# Hive_1_6.net
KiCad netlist of a schematic drawn in EAGLE
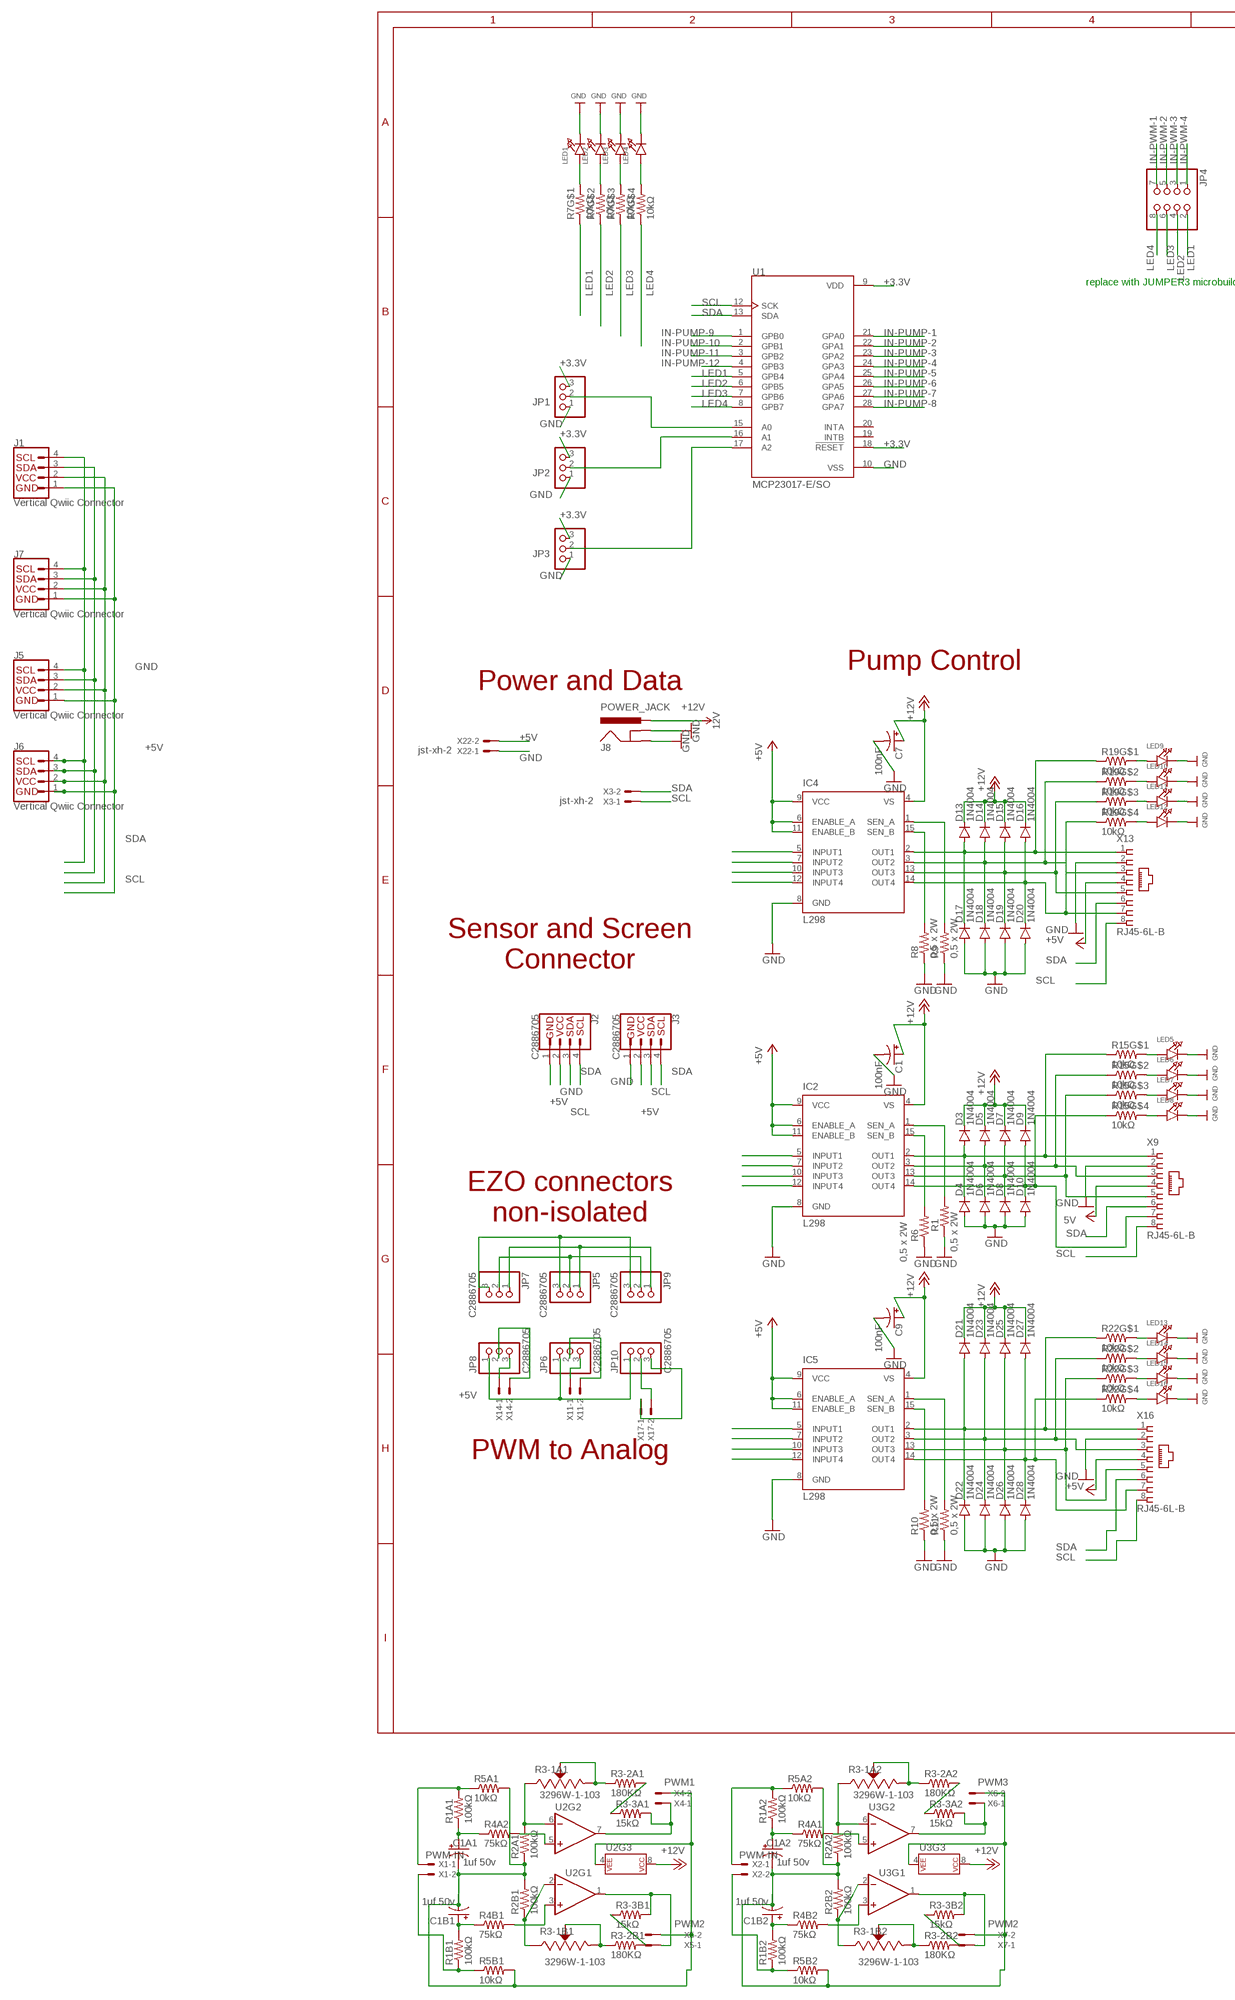
[diagram p0: schematic, sheet 1, part 1 of 2]
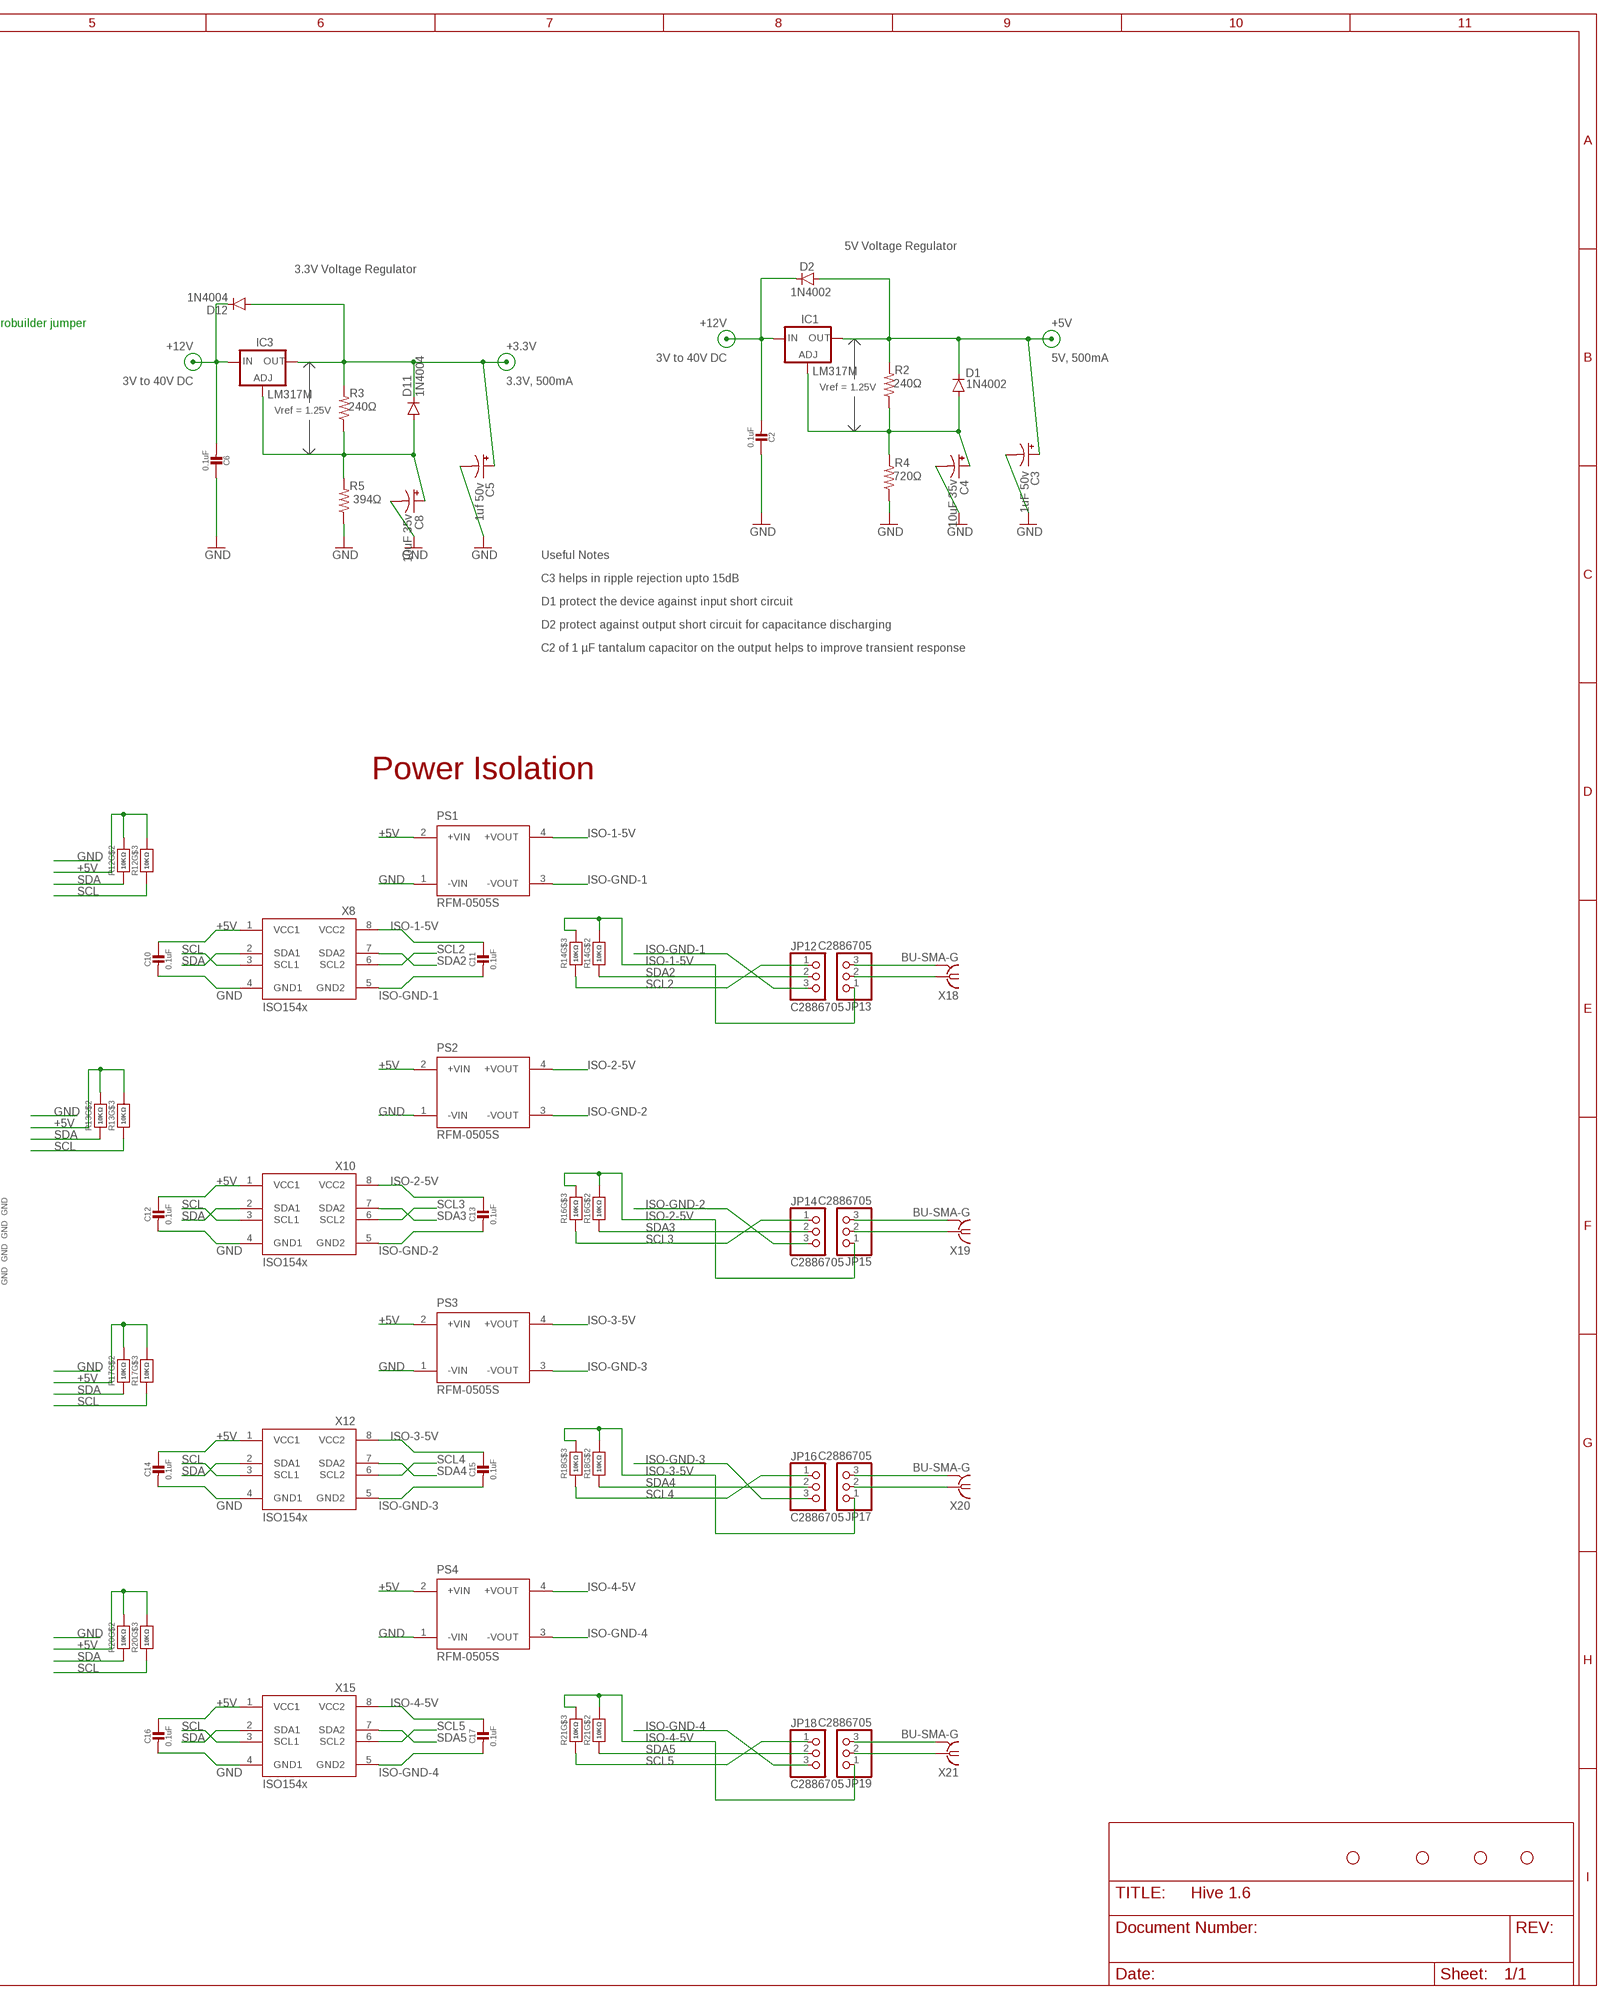
[diagram p1: schematic, sheet 1, part 2 of 2]

(export (version "E")
  (design (tool "Eeschema 10.0.6"))
  (components
    (comp (ref "C1")
      (value "100nF")
      (footprint "eagle-import:UD-4X5,8_NICHICON")
      (libsource (lib "eagle-import") (part "CPOL-USUD-4X5,8"))
    )
    (comp (ref "C1A1")
      (value "1uf 50v")
      (footprint "eagle-import:UD-4X5,8_NICHICON")
      (libsource (lib "eagle-import") (part "CPOL-USUD-4X5,8"))
    )
    (comp (ref "C1A2")
      (value "1uf 50v")
      (footprint "eagle-import:UD-4X5,8_NICHICON")
      (libsource (lib "eagle-import") (part "CPOL-USUD-4X5,8"))
    )
    (comp (ref "C1B1")
      (value "1uf 50v")
      (footprint "eagle-import:UD-4X5,8_NICHICON")
      (libsource (lib "eagle-import") (part "CPOL-USUD-4X5,8"))
    )
    (comp (ref "C1B2")
      (value "1uf 50v")
      (footprint "eagle-import:UD-4X5,8_NICHICON")
      (libsource (lib "eagle-import") (part "CPOL-USUD-4X5,8"))
    )
    (comp (ref "C2")
      (value "0.1uF")
      (footprint "eagle-import:0603-NO")
      (libsource (lib "eagle-import") (part "CAP_CERAMIC0603_NO"))
    )
    (comp (ref "C3")
      (value "1uF 50v")
      (footprint "eagle-import:UD-4X5,8_NICHICON")
      (libsource (lib "eagle-import") (part "CPOL-USUD-4X5,8"))
    )
    (comp (ref "C4")
      (value "10uF 35v")
      (footprint "eagle-import:UD-4X5,8_NICHICON")
      (libsource (lib "eagle-import") (part "CPOL-USUD-4X5,8"))
    )
    (comp (ref "C5")
      (value "1uf 50v")
      (footprint "eagle-import:UD-4X5,8_NICHICON")
      (libsource (lib "eagle-import") (part "CPOL-USUD-4X5,8"))
    )
    (comp (ref "C6")
      (value "0.1uF")
      (footprint "eagle-import:0603-NO")
      (libsource (lib "eagle-import") (part "CAP_CERAMIC0603_NO"))
    )
    (comp (ref "C7")
      (value "100nF")
      (footprint "eagle-import:UD-4X5,8_NICHICON")
      (libsource (lib "eagle-import") (part "CPOL-USUD-4X5,8"))
    )
    (comp (ref "C8")
      (value "10uF 35v")
      (footprint "eagle-import:UD-4X5,8_NICHICON")
      (libsource (lib "eagle-import") (part "CPOL-USUD-4X5,8"))
    )
    (comp (ref "C9")
      (value "100nF")
      (footprint "eagle-import:UD-4X5,8_NICHICON")
      (libsource (lib "eagle-import") (part "CPOL-USUD-4X5,8"))
    )
    (comp (ref "C10")
      (value "0.1uF")
      (footprint "eagle-import:0603-NO")
      (libsource (lib "eagle-import") (part "CAP_CERAMIC0603_NO"))
    )
    (comp (ref "C11")
      (value "0.1uF")
      (footprint "eagle-import:0603-NO")
      (libsource (lib "eagle-import") (part "CAP_CERAMIC0603_NO"))
    )
    (comp (ref "C12")
      (value "0.1uF")
      (footprint "eagle-import:0603-NO")
      (libsource (lib "eagle-import") (part "CAP_CERAMIC0603_NO"))
    )
    (comp (ref "C13")
      (value "0.1uF")
      (footprint "eagle-import:0603-NO")
      (libsource (lib "eagle-import") (part "CAP_CERAMIC0603_NO"))
    )
    (comp (ref "C14")
      (value "0.1uF")
      (footprint "eagle-import:0603-NO")
      (libsource (lib "eagle-import") (part "CAP_CERAMIC0603_NO"))
    )
    (comp (ref "C15")
      (value "0.1uF")
      (footprint "eagle-import:0603-NO")
      (libsource (lib "eagle-import") (part "CAP_CERAMIC0603_NO"))
    )
    (comp (ref "C16")
      (value "0.1uF")
      (footprint "eagle-import:0603-NO")
      (libsource (lib "eagle-import") (part "CAP_CERAMIC0603_NO"))
    )
    (comp (ref "C17")
      (value "0.1uF")
      (footprint "eagle-import:0603-NO")
      (libsource (lib "eagle-import") (part "CAP_CERAMIC0603_NO"))
    )
    (comp (ref "D1")
      (value "1N4002")
      (footprint "eagle-import:DO214BA")
      (libsource (lib "eagle-import") (part "DIODE-DO214BA"))
    )
    (comp (ref "D2")
      (value "1N4002")
      (footprint "eagle-import:DO214BA")
      (libsource (lib "eagle-import") (part "DIODE-DO214BA"))
    )
    (comp (ref "D3")
      (value "1N4004")
      (footprint "eagle-import:DO214BA")
      (libsource (lib "eagle-import") (part "DIODE-DO214BA"))
    )
    (comp (ref "D4")
      (value "1N4004")
      (footprint "eagle-import:DO214BA")
      (libsource (lib "eagle-import") (part "DIODE-DO214BA"))
    )
    (comp (ref "D5")
      (value "1N4004")
      (footprint "eagle-import:DO214BA")
      (libsource (lib "eagle-import") (part "DIODE-DO214BA"))
    )
    (comp (ref "D6")
      (value "1N4004")
      (footprint "eagle-import:DO214BA")
      (libsource (lib "eagle-import") (part "DIODE-DO214BA"))
    )
    (comp (ref "D7")
      (value "1N4004")
      (footprint "eagle-import:DO214BA")
      (libsource (lib "eagle-import") (part "DIODE-DO214BA"))
    )
    (comp (ref "D8")
      (value "1N4004")
      (footprint "eagle-import:DO214BA")
      (libsource (lib "eagle-import") (part "DIODE-DO214BA"))
    )
    (comp (ref "D9")
      (value "1N4004")
      (footprint "eagle-import:DO214BA")
      (libsource (lib "eagle-import") (part "DIODE-DO214BA"))
    )
    (comp (ref "D10")
      (value "1N4004")
      (footprint "eagle-import:DO214BA")
      (libsource (lib "eagle-import") (part "DIODE-DO214BA"))
    )
    (comp (ref "D11")
      (value "1N4004")
      (footprint "eagle-import:DO214BA")
      (libsource (lib "eagle-import") (part "DIODE-DO214BA"))
    )
    (comp (ref "D12")
      (value "1N4004")
      (footprint "eagle-import:DO214BA")
      (libsource (lib "eagle-import") (part "DIODE-DO214BA"))
    )
    (comp (ref "D13")
      (value "1N4004")
      (footprint "eagle-import:DO214BA")
      (libsource (lib "eagle-import") (part "DIODE-DO214BA"))
    )
    (comp (ref "D14")
      (value "1N4004")
      (footprint "eagle-import:DO214BA")
      (libsource (lib "eagle-import") (part "DIODE-DO214BA"))
    )
    (comp (ref "D15")
      (value "1N4004")
      (footprint "eagle-import:DO214BA")
      (libsource (lib "eagle-import") (part "DIODE-DO214BA"))
    )
    (comp (ref "D16")
      (value "1N4004")
      (footprint "eagle-import:DO214BA")
      (libsource (lib "eagle-import") (part "DIODE-DO214BA"))
    )
    (comp (ref "D17")
      (value "1N4004")
      (footprint "eagle-import:DO214BA")
      (libsource (lib "eagle-import") (part "DIODE-DO214BA"))
    )
    (comp (ref "D18")
      (value "1N4004")
      (footprint "eagle-import:DO214BA")
      (libsource (lib "eagle-import") (part "DIODE-DO214BA"))
    )
    (comp (ref "D19")
      (value "1N4004")
      (footprint "eagle-import:DO214BA")
      (libsource (lib "eagle-import") (part "DIODE-DO214BA"))
    )
    (comp (ref "D20")
      (value "1N4004")
      (footprint "eagle-import:DO214BA")
      (libsource (lib "eagle-import") (part "DIODE-DO214BA"))
    )
    (comp (ref "D21")
      (value "1N4004")
      (footprint "eagle-import:DO214BA")
      (libsource (lib "eagle-import") (part "DIODE-DO214BA"))
    )
    (comp (ref "D22")
      (value "1N4004")
      (footprint "eagle-import:DO214BA")
      (libsource (lib "eagle-import") (part "DIODE-DO214BA"))
    )
    (comp (ref "D23")
      (value "1N4004")
      (footprint "eagle-import:DO214BA")
      (libsource (lib "eagle-import") (part "DIODE-DO214BA"))
    )
    (comp (ref "D24")
      (value "1N4004")
      (footprint "eagle-import:DO214BA")
      (libsource (lib "eagle-import") (part "DIODE-DO214BA"))
    )
    (comp (ref "D25")
      (value "1N4004")
      (footprint "eagle-import:DO214BA")
      (libsource (lib "eagle-import") (part "DIODE-DO214BA"))
    )
    (comp (ref "D26")
      (value "1N4004")
      (footprint "eagle-import:DO214BA")
      (libsource (lib "eagle-import") (part "DIODE-DO214BA"))
    )
    (comp (ref "D27")
      (value "1N4004")
      (footprint "eagle-import:DO214BA")
      (libsource (lib "eagle-import") (part "DIODE-DO214BA"))
    )
    (comp (ref "D28")
      (value "1N4004")
      (footprint "eagle-import:DO214BA")
      (libsource (lib "eagle-import") (part "DIODE-DO214BA"))
    )
    (comp (ref "H1")
      (value "STAND-OFF")
      (footprint "eagle-import:STAND-OFF")
      (libsource (lib "eagle-import") (part "STAND-OFF"))
    )
    (comp (ref "H2")
      (value "STAND-OFF")
      (footprint "eagle-import:STAND-OFF")
      (libsource (lib "eagle-import") (part "STAND-OFF"))
    )
    (comp (ref "H3")
      (value "STAND-OFF")
      (footprint "eagle-import:STAND-OFF")
      (libsource (lib "eagle-import") (part "STAND-OFF"))
    )
    (comp (ref "H4")
      (value "STAND-OFF")
      (footprint "eagle-import:STAND-OFF")
      (libsource (lib "eagle-import") (part "STAND-OFF"))
    )
    (comp (ref "IC1")
      (value "LM317MBSTT3")
      (footprint "eagle-import:SOT223")
      (fields (field (name "PARTNUMBER") "LM317M"))
      (libsource (lib "eagle-import") (part "LM317?MBSTT3"))
    )
    (comp (ref "IC2")
      (value "L298")
      (footprint "eagle-import:MULTIWATT-15")
      (fields (field (name "MPN") "L298N"))
      (libsource (lib "eagle-import") (part "L298"))
    )
    (comp (ref "IC3")
      (value "LM317MBSTT3")
      (footprint "eagle-import:SOT223")
      (fields (field (name "PARTNUMBER") "LM317M"))
      (libsource (lib "eagle-import") (part "LM317?MBSTT3"))
    )
    (comp (ref "IC4")
      (value "L298")
      (footprint "eagle-import:MULTIWATT-15")
      (fields (field (name "MPN") "L298N"))
      (libsource (lib "eagle-import") (part "L298"))
    )
    (comp (ref "IC5")
      (value "L298")
      (footprint "eagle-import:MULTIWATT-15")
      (fields (field (name "MPN") "L298N"))
      (libsource (lib "eagle-import") (part "L298"))
    )
    (comp (ref "J1")
      (value "Vertical Qwiic Connector")
      (footprint "eagle-import:JST04_1MM_VERT")
      (libsource (lib "eagle-import") (part "QWIIC_CONNECTOR"))
    )
    (comp (ref "J2")
      (value "C2886705")
      (footprint "eagle-import:1X04")
      (libsource (lib "eagle-import") (part "I2C_STANDARD"))
    )
    (comp (ref "J3")
      (value "C2886705")
      (footprint "eagle-import:1X04")
      (libsource (lib "eagle-import") (part "I2C_STANDARD"))
    )
    (comp (ref "J5")
      (value "Vertical Qwiic Connector")
      (footprint "eagle-import:JST04_1MM_VERT")
      (libsource (lib "eagle-import") (part "QWIIC_CONNECTOR"))
    )
    (comp (ref "J6")
      (value "Vertical Qwiic Connector")
      (footprint "eagle-import:JST04_1MM_VERT")
      (libsource (lib "eagle-import") (part "QWIIC_CONNECTOR"))
    )
    (comp (ref "J7")
      (value "Vertical Qwiic Connector")
      (footprint "eagle-import:JST04_1MM_VERT")
      (libsource (lib "eagle-import") (part "QWIIC_CONNECTOR"))
    )
    (comp (ref "J8")
      (value "POWER_JACK")
      (footprint "eagle-import:POWER_JACK_PTH")
      (libsource (lib "eagle-import") (part "POWER_JACK"))
    )
    (comp (ref "JP1")
      (value "HEADER-1X3ROUND")
      (footprint "eagle-import:1X03_ROUND")
      (libsource (lib "eagle-import") (part "HEADER-1X3ROUND"))
    )
    (comp (ref "JP2")
      (value "HEADER-1X3ROUND")
      (footprint "eagle-import:1X03_ROUND")
      (libsource (lib "eagle-import") (part "HEADER-1X3ROUND"))
    )
    (comp (ref "JP3")
      (value "HEADER-1X3ROUND")
      (footprint "eagle-import:1X03_ROUND")
      (libsource (lib "eagle-import") (part "HEADER-1X3ROUND"))
    )
    (comp (ref "JP4")
      (value "PINHD-2X4")
      (footprint "eagle-import:2X04")
      (libsource (lib "eagle-import") (part "PINHD-2X4"))
    )
    (comp (ref "JP5")
      (value "C2886705")
      (footprint "eagle-import:1X03-CLEANBIG")
      (libsource (lib "eagle-import") (part "PINHD-1X3CB"))
    )
    (comp (ref "JP6")
      (value "C2886705")
      (footprint "eagle-import:1X03-CLEANBIG")
      (libsource (lib "eagle-import") (part "PINHD-1X3CB"))
    )
    (comp (ref "JP7")
      (value "C2886705")
      (footprint "eagle-import:1X03-CLEANBIG")
      (libsource (lib "eagle-import") (part "PINHD-1X3CB"))
    )
    (comp (ref "JP8")
      (value "C2886705")
      (footprint "eagle-import:1X03-CLEANBIG")
      (libsource (lib "eagle-import") (part "PINHD-1X3CB"))
    )
    (comp (ref "JP9")
      (value "C2886705")
      (footprint "eagle-import:1X03-CLEANBIG")
      (libsource (lib "eagle-import") (part "PINHD-1X3CB"))
    )
    (comp (ref "JP10")
      (value "C2886705")
      (footprint "eagle-import:1X03-CLEANBIG")
      (libsource (lib "eagle-import") (part "PINHD-1X3CB"))
    )
    (comp (ref "JP12")
      (value "C2886705")
      (footprint "eagle-import:1X03-CLEANBIG")
      (libsource (lib "eagle-import") (part "PINHD-1X3CB"))
    )
    (comp (ref "JP13")
      (value "C2886705")
      (footprint "eagle-import:1X03-CLEANBIG")
      (libsource (lib "eagle-import") (part "PINHD-1X3CB"))
    )
    (comp (ref "JP14")
      (value "C2886705")
      (footprint "eagle-import:1X03-CLEANBIG")
      (libsource (lib "eagle-import") (part "PINHD-1X3CB"))
    )
    (comp (ref "JP15")
      (value "C2886705")
      (footprint "eagle-import:1X03-CLEANBIG")
      (libsource (lib "eagle-import") (part "PINHD-1X3CB"))
    )
    (comp (ref "JP16")
      (value "C2886705")
      (footprint "eagle-import:1X03-CLEANBIG")
      (libsource (lib "eagle-import") (part "PINHD-1X3CB"))
    )
    (comp (ref "JP17")
      (value "C2886705")
      (footprint "eagle-import:1X03-CLEANBIG")
      (libsource (lib "eagle-import") (part "PINHD-1X3CB"))
    )
    (comp (ref "JP18")
      (value "C2886705")
      (footprint "eagle-import:1X03-CLEANBIG")
      (libsource (lib "eagle-import") (part "PINHD-1X3CB"))
    )
    (comp (ref "JP19")
      (value "C2886705")
      (footprint "eagle-import:1X03-CLEANBIG")
      (libsource (lib "eagle-import") (part "PINHD-1X3CB"))
    )
    (comp (ref "LED1")
      (value "LED0603")
      (footprint "eagle-import:CHIPLED_0603")
      (libsource (lib "eagle-import") (part "LED0603"))
    )
    (comp (ref "LED2")
      (value "LED0603")
      (footprint "eagle-import:CHIPLED_0603")
      (libsource (lib "eagle-import") (part "LED0603"))
    )
    (comp (ref "LED3")
      (value "LED0603")
      (footprint "eagle-import:CHIPLED_0603")
      (libsource (lib "eagle-import") (part "LED0603"))
    )
    (comp (ref "LED4")
      (value "LED0603")
      (footprint "eagle-import:CHIPLED_0603")
      (libsource (lib "eagle-import") (part "LED0603"))
    )
    (comp (ref "LED5")
      (value "LED0603")
      (footprint "eagle-import:CHIPLED_0603")
      (libsource (lib "eagle-import") (part "LED0603"))
    )
    (comp (ref "LED6")
      (value "LED0603")
      (footprint "eagle-import:CHIPLED_0603")
      (libsource (lib "eagle-import") (part "LED0603"))
    )
    (comp (ref "LED7")
      (value "LED0603")
      (footprint "eagle-import:CHIPLED_0603")
      (libsource (lib "eagle-import") (part "LED0603"))
    )
    (comp (ref "LED8")
      (value "LED0603")
      (footprint "eagle-import:CHIPLED_0603")
      (libsource (lib "eagle-import") (part "LED0603"))
    )
    (comp (ref "LED9")
      (value "LED0603")
      (footprint "eagle-import:CHIPLED_0603")
      (libsource (lib "eagle-import") (part "LED0603"))
    )
    (comp (ref "LED10")
      (value "LED0603")
      (footprint "eagle-import:CHIPLED_0603")
      (libsource (lib "eagle-import") (part "LED0603"))
    )
    (comp (ref "LED11")
      (value "LED0603")
      (footprint "eagle-import:CHIPLED_0603")
      (libsource (lib "eagle-import") (part "LED0603"))
    )
    (comp (ref "LED12")
      (value "LED0603")
      (footprint "eagle-import:CHIPLED_0603")
      (libsource (lib "eagle-import") (part "LED0603"))
    )
    (comp (ref "LED13")
      (value "LED0603")
      (footprint "eagle-import:CHIPLED_0603")
      (libsource (lib "eagle-import") (part "LED0603"))
    )
    (comp (ref "LED14")
      (value "LED0603")
      (footprint "eagle-import:CHIPLED_0603")
      (libsource (lib "eagle-import") (part "LED0603"))
    )
    (comp (ref "LED15")
      (value "LED0603")
      (footprint "eagle-import:CHIPLED_0603")
      (libsource (lib "eagle-import") (part "LED0603"))
    )
    (comp (ref "LED16")
      (value "LED0603")
      (footprint "eagle-import:CHIPLED_0603")
      (libsource (lib "eagle-import") (part "LED0603"))
    )
    (comp (ref "PS1")
      (value "RFM-0505S")
      (footprint "eagle-import:CONV_RFM-0505S")
      (fields (field (name "MF") "Recom Power"))
      (libsource (lib "eagle-import") (part "RFM-0505S"))
    )
    (comp (ref "PS2")
      (value "RFM-0505S")
      (footprint "eagle-import:CONV_RFM-0505S")
      (fields (field (name "MF") "Recom Power"))
      (libsource (lib "eagle-import") (part "RFM-0505S"))
    )
    (comp (ref "PS3")
      (value "RFM-0505S")
      (footprint "eagle-import:CONV_RFM-0505S")
      (fields (field (name "MF") "Recom Power"))
      (libsource (lib "eagle-import") (part "RFM-0505S"))
    )
    (comp (ref "PS4")
      (value "RFM-0505S")
      (footprint "eagle-import:CONV_RFM-0505S")
      (fields (field (name "MF") "Recom Power"))
      (libsource (lib "eagle-import") (part "RFM-0505S"))
    )
    (comp (ref "R1")
      (value "0,5 x 2W")
      (footprint "eagle-import:R2512")
      (libsource (lib "eagle-import") (part "R-US_R2512"))
    )
    (comp (ref "R1A1")
      (value "100kΩ")
      (footprint "eagle-import:M1206")
      (libsource (lib "eagle-import") (part "adafruit_420_R-US_M1206"))
    )
    (comp (ref "R1A2")
      (value "100kΩ")
      (footprint "eagle-import:M1206")
      (libsource (lib "eagle-import") (part "adafruit_420_R-US_M1206"))
    )
    (comp (ref "R1B1")
      (value "100kΩ")
      (footprint "eagle-import:M1206")
      (libsource (lib "eagle-import") (part "adafruit_420_R-US_M1206"))
    )
    (comp (ref "R1B2")
      (value "100kΩ")
      (footprint "eagle-import:M1206")
      (libsource (lib "eagle-import") (part "adafruit_420_R-US_M1206"))
    )
    (comp (ref "R2")
      (value "240Ω")
      (footprint "eagle-import:M0805")
      (libsource (lib "eagle-import") (part "resistor_R-US_M0805"))
    )
    (comp (ref "R2A1")
      (value "100kΩ")
      (footprint "eagle-import:M1206")
      (libsource (lib "eagle-import") (part "adafruit_420_R-US_M1206"))
    )
    (comp (ref "R2A2")
      (value "100kΩ")
      (footprint "eagle-import:M1206")
      (libsource (lib "eagle-import") (part "adafruit_420_R-US_M1206"))
    )
    (comp (ref "R2B1")
      (value "100kΩ")
      (footprint "eagle-import:M1206")
      (libsource (lib "eagle-import") (part "adafruit_420_R-US_M1206"))
    )
    (comp (ref "R2B2")
      (value "100kΩ")
      (footprint "eagle-import:M1206")
      (libsource (lib "eagle-import") (part "adafruit_420_R-US_M1206"))
    )
    (comp (ref "R3")
      (value "240Ω")
      (footprint "eagle-import:M0805")
      (libsource (lib "eagle-import") (part "resistor_R-US_M0805"))
    )
    (comp (ref "R3-1A1")
      (value "3296W-1-103")
      (footprint "eagle-import:TRIM_3296W-1-103")
      (fields (field (name "MF") "Bourns"))
      (libsource (lib "eagle-import") (part "3296W-1-103"))
    )
    (comp (ref "R3-1A2")
      (value "3296W-1-103")
      (footprint "eagle-import:TRIM_3296W-1-103")
      (fields (field (name "MF") "Bourns"))
      (libsource (lib "eagle-import") (part "3296W-1-103"))
    )
    (comp (ref "R3-1B1")
      (value "3296W-1-103")
      (footprint "eagle-import:TRIM_3296W-1-103")
      (fields (field (name "MF") "Bourns"))
      (libsource (lib "eagle-import") (part "3296W-1-103"))
    )
    (comp (ref "R3-1B2")
      (value "3296W-1-103")
      (footprint "eagle-import:TRIM_3296W-1-103")
      (fields (field (name "MF") "Bourns"))
      (libsource (lib "eagle-import") (part "3296W-1-103"))
    )
    (comp (ref "R3-2A1")
      (value "180KΩ")
      (footprint "eagle-import:M1206")
      (libsource (lib "eagle-import") (part "adafruit_420_R-US_M1206"))
    )
    (comp (ref "R3-2A2")
      (value "180KΩ")
      (footprint "eagle-import:M1206")
      (libsource (lib "eagle-import") (part "adafruit_420_R-US_M1206"))
    )
    (comp (ref "R3-2B1")
      (value "180KΩ")
      (footprint "eagle-import:M1206")
      (libsource (lib "eagle-import") (part "adafruit_420_R-US_M1206"))
    )
    (comp (ref "R3-2B2")
      (value "180KΩ")
      (footprint "eagle-import:M1206")
      (libsource (lib "eagle-import") (part "adafruit_420_R-US_M1206"))
    )
    (comp (ref "R3-3A1")
      (value "15kΩ")
      (footprint "eagle-import:M1206")
      (libsource (lib "eagle-import") (part "adafruit_420_R-US_M1206"))
    )
    (comp (ref "R3-3A2")
      (value "15kΩ")
      (footprint "eagle-import:M1206")
      (libsource (lib "eagle-import") (part "adafruit_420_R-US_M1206"))
    )
    (comp (ref "R3-3B1")
      (value "15kΩ")
      (footprint "eagle-import:M1206")
      (libsource (lib "eagle-import") (part "adafruit_420_R-US_M1206"))
    )
    (comp (ref "R3-3B2")
      (value "15kΩ")
      (footprint "eagle-import:M1206")
      (libsource (lib "eagle-import") (part "adafruit_420_R-US_M1206"))
    )
    (comp (ref "R4")
      (value "720Ω")
      (footprint "eagle-import:M0805")
      (libsource (lib "eagle-import") (part "resistor_R-US_M0805"))
    )
    (comp (ref "R4A1")
      (value "75kΩ")
      (footprint "eagle-import:M1206")
      (libsource (lib "eagle-import") (part "adafruit_420_R-US_M1206"))
    )
    (comp (ref "R4A2")
      (value "75kΩ")
      (footprint "eagle-import:M1206")
      (libsource (lib "eagle-import") (part "adafruit_420_R-US_M1206"))
    )
    (comp (ref "R4B1")
      (value "75kΩ")
      (footprint "eagle-import:M1206")
      (libsource (lib "eagle-import") (part "adafruit_420_R-US_M1206"))
    )
    (comp (ref "R4B2")
      (value "75kΩ")
      (footprint "eagle-import:M1206")
      (libsource (lib "eagle-import") (part "adafruit_420_R-US_M1206"))
    )
    (comp (ref "R5")
      (value "394Ω")
      (footprint "eagle-import:M0805")
      (libsource (lib "eagle-import") (part "resistor_R-US_M0805"))
    )
    (comp (ref "R5A1")
      (value "10kΩ")
      (footprint "eagle-import:M1206")
      (libsource (lib "eagle-import") (part "adafruit_420_R-US_M1206"))
    )
    (comp (ref "R5A2")
      (value "10kΩ")
      (footprint "eagle-import:M1206")
      (libsource (lib "eagle-import") (part "adafruit_420_R-US_M1206"))
    )
    (comp (ref "R5B1")
      (value "10kΩ")
      (footprint "eagle-import:M1206")
      (libsource (lib "eagle-import") (part "adafruit_420_R-US_M1206"))
    )
    (comp (ref "R5B2")
      (value "10kΩ")
      (footprint "eagle-import:M1206")
      (libsource (lib "eagle-import") (part "adafruit_420_R-US_M1206"))
    )
    (comp (ref "R6")
      (value "0,5 x 2W")
      (footprint "eagle-import:R2512")
      (libsource (lib "eagle-import") (part "R-US_R2512"))
    )
    (comp (ref "R7")
      (value "10kΩ")
      (footprint "eagle-import:RESPACK_4X0603")
      (libsource (lib "eagle-import") (part "RESISTOR_4PACK_US"))
    )
    (comp (ref "R8")
      (value "0,5 x 2W")
      (footprint "eagle-import:R2512")
      (libsource (lib "eagle-import") (part "R-US_R2512"))
    )
    (comp (ref "R9")
      (value "0,5 x 2W")
      (footprint "eagle-import:R2512")
      (libsource (lib "eagle-import") (part "R-US_R2512"))
    )
    (comp (ref "R10")
      (value "0,5 x 2W")
      (footprint "eagle-import:R2512")
      (libsource (lib "eagle-import") (part "R-US_R2512"))
    )
    (comp (ref "R11")
      (value "0,5 x 2W")
      (footprint "eagle-import:R2512")
      (libsource (lib "eagle-import") (part "R-US_R2512"))
    )
    (comp (ref "R12")
      (value "10KΩ")
      (footprint "eagle-import:RESPACK_4X0603")
      (libsource (lib "eagle-import") (part "RESISTOR_4PACK"))
    )
    (comp (ref "R13")
      (value "10KΩ")
      (footprint "eagle-import:RESPACK_4X0603")
      (libsource (lib "eagle-import") (part "RESISTOR_4PACK"))
    )
    (comp (ref "R14")
      (value "10KΩ")
      (footprint "eagle-import:RESPACK_4X0603")
      (libsource (lib "eagle-import") (part "RESISTOR_4PACK"))
    )
    (comp (ref "R15")
      (value "10kΩ")
      (footprint "eagle-import:RESPACK_4X0603")
      (libsource (lib "eagle-import") (part "RESISTOR_4PACK_US"))
    )
    (comp (ref "R16")
      (value "10KΩ")
      (footprint "eagle-import:RESPACK_4X0603")
      (libsource (lib "eagle-import") (part "RESISTOR_4PACK"))
    )
    (comp (ref "R17")
      (value "10KΩ")
      (footprint "eagle-import:RESPACK_4X0603")
      (libsource (lib "eagle-import") (part "RESISTOR_4PACK"))
    )
    (comp (ref "R18")
      (value "10KΩ")
      (footprint "eagle-import:RESPACK_4X0603")
      (libsource (lib "eagle-import") (part "RESISTOR_4PACK"))
    )
    (comp (ref "R19")
      (value "10kΩ")
      (footprint "eagle-import:RESPACK_4X0603")
      (libsource (lib "eagle-import") (part "RESISTOR_4PACK_US"))
    )
    (comp (ref "R20")
      (value "10KΩ")
      (footprint "eagle-import:RESPACK_4X0603")
      (libsource (lib "eagle-import") (part "RESISTOR_4PACK"))
    )
    (comp (ref "R21")
      (value "10KΩ")
      (footprint "eagle-import:RESPACK_4X0603")
      (libsource (lib "eagle-import") (part "RESISTOR_4PACK"))
    )
    (comp (ref "R22")
      (value "10kΩ")
      (footprint "eagle-import:RESPACK_4X0603")
      (libsource (lib "eagle-import") (part "RESISTOR_4PACK_US"))
    )
    (comp (ref "U1")
      (value "MCP23017-E/SO")
      (footprint "eagle-import:SOIC127P1030X265-28N")
      (fields (field (name "MF") "Microchip"))
      (libsource (lib "eagle-import") (part "MCP23017-E/SO"))
    )
    (comp (ref "U2")
      (value "LM358")
      (footprint "eagle-import:SO08")
      (libsource (lib "eagle-import") (part "LM358SO08"))
    )
    (comp (ref "U3")
      (value "LM358")
      (footprint "eagle-import:SO08")
      (libsource (lib "eagle-import") (part "LM358SO08"))
    )
    (comp (ref "X1")
      (value "PWM-IN")
      (footprint "eagle-import:JST-XH-02-PACKAGE-LONG-PAD")
      (libsource (lib "eagle-import") (part "JST-XH-02-PIN-LONG-PAD"))
    )
    (comp (ref "X2")
      (value "PWM-IN")
      (footprint "eagle-import:JST-XH-02-PACKAGE-LONG-PAD")
      (libsource (lib "eagle-import") (part "JST-XH-02-PIN-LONG-PAD"))
    )
    (comp (ref "X3")
      (value "jst-xh-2")
      (footprint "eagle-import:JST-XH-02-PACKAGE-LONG-PAD")
      (libsource (lib "eagle-import") (part "JST-XH-02-PIN-LONG-PAD"))
    )
    (comp (ref "X4")
      (value "PWM1")
      (footprint "eagle-import:JST-XH-02-PACKAGE-LONG-PAD")
      (libsource (lib "eagle-import") (part "JST-XH-02-PIN-LONG-PAD"))
    )
    (comp (ref "X5")
      (value "PWM2")
      (footprint "eagle-import:JST-XH-02-PACKAGE-LONG-PAD")
      (libsource (lib "eagle-import") (part "JST-XH-02-PIN-LONG-PAD"))
    )
    (comp (ref "X6")
      (value "PWM3")
      (footprint "eagle-import:JST-XH-02-PACKAGE-LONG-PAD")
      (libsource (lib "eagle-import") (part "JST-XH-02-PIN-LONG-PAD"))
    )
    (comp (ref "X7")
      (value "PWM2")
      (footprint "eagle-import:JST-XH-02-PACKAGE-LONG-PAD")
      (libsource (lib "eagle-import") (part "JST-XH-02-PIN-LONG-PAD"))
    )
    (comp (ref "X8")
      (value "ISO154X")
      (footprint "eagle-import:SOIC8_150MIL")
      (libsource (lib "eagle-import") (part "ISO154X"))
    )
    (comp (ref "X9")
      (value "RJ45-6L-B")
      (footprint "eagle-import:RJ45-NO-SHIELD")
      (libsource (lib "eagle-import") (part "RJ45-6L-B"))
    )
    (comp (ref "X10")
      (value "ISO154X")
      (footprint "eagle-import:SOIC8_150MIL")
      (libsource (lib "eagle-import") (part "ISO154X"))
    )
    (comp (ref "X11")
      (value "jst-xh-2")
      (footprint "eagle-import:JST-XH-02-PACKAGE-LONG-PAD")
      (libsource (lib "eagle-import") (part "JST-XH-02-PIN-LONG-PAD"))
    )
    (comp (ref "X12")
      (value "ISO154X")
      (footprint "eagle-import:SOIC8_150MIL")
      (libsource (lib "eagle-import") (part "ISO154X"))
    )
    (comp (ref "X13")
      (value "RJ45-6L-B")
      (footprint "eagle-import:RJ45-NO-SHIELD")
      (libsource (lib "eagle-import") (part "RJ45-6L-B"))
    )
    (comp (ref "X14")
      (value "jst-xh-2")
      (footprint "eagle-import:JST-XH-02-PACKAGE-LONG-PAD")
      (libsource (lib "eagle-import") (part "JST-XH-02-PIN-LONG-PAD"))
    )
    (comp (ref "X15")
      (value "ISO154X")
      (footprint "eagle-import:SOIC8_150MIL")
      (libsource (lib "eagle-import") (part "ISO154X"))
    )
    (comp (ref "X16")
      (value "RJ45-6L-B")
      (footprint "eagle-import:RJ45-NO-SHIELD")
      (libsource (lib "eagle-import") (part "RJ45-6L-B"))
    )
    (comp (ref "X17")
      (value "jst-xh-2")
      (footprint "eagle-import:JST-XH-02-PACKAGE-LONG-PAD")
      (libsource (lib "eagle-import") (part "JST-XH-02-PIN-LONG-PAD"))
    )
    (comp (ref "X18")
      (value "BU-SMA-G")
      (footprint "eagle-import:BU-SMA-G")
      (libsource (lib "eagle-import") (part "BU-SMA-G"))
    )
    (comp (ref "X19")
      (value "BU-SMA-G")
      (footprint "eagle-import:BU-SMA-G")
      (libsource (lib "eagle-import") (part "BU-SMA-G"))
    )
    (comp (ref "X20")
      (value "BU-SMA-G")
      (footprint "eagle-import:BU-SMA-G")
      (libsource (lib "eagle-import") (part "BU-SMA-G"))
    )
    (comp (ref "X21")
      (value "BU-SMA-G")
      (footprint "eagle-import:BU-SMA-G")
      (libsource (lib "eagle-import") (part "BU-SMA-G"))
    )
    (comp (ref "X22")
      (value "jst-xh-2")
      (footprint "eagle-import:JST-XH-02-PACKAGE-LONG-PAD")
      (libsource (lib "eagle-import") (part "JST-XH-02-PIN-LONG-PAD"))
    )
  )
  (nets
    (net (code "1") (name "+3V3") (class "Default")
      (node (ref "C10") (pin "1") (pinfunction "1_1") (pintype "passive"))
      (node (ref "C12") (pin "1") (pinfunction "1_1") (pintype "passive"))
      (node (ref "C14") (pin "1") (pinfunction "1_1") (pintype "passive"))
      (node (ref "C16") (pin "1") (pinfunction "1_1") (pintype "passive"))
      (node (ref "C3") (pin "+") (pinfunction "+_+") (pintype "passive"))
      (node (ref "D1") (pin "C") (pinfunction "C_C") (pintype "passive"))
      (node (ref "D2") (pin "A") (pinfunction "A_A") (pintype "passive"))
      (node (ref "IC1") (pin "4") (pinfunction "OUT_4") (pintype "passive"))
      (node (ref "IC2") (pin "11") (pinfunction "ENABLE_B_11") (pintype "input"))
      (node (ref "IC2") (pin "6") (pinfunction "ENABLE_A_6") (pintype "input"))
      (node (ref "IC2") (pin "9") (pinfunction "VCC_9") (pintype "power_in"))
      (node (ref "IC4") (pin "11") (pinfunction "ENABLE_B_11") (pintype "input"))
      (node (ref "IC4") (pin "6") (pinfunction "ENABLE_A_6") (pintype "input"))
      (node (ref "IC4") (pin "9") (pinfunction "VCC_9") (pintype "power_in"))
      (node (ref "IC5") (pin "11") (pinfunction "ENABLE_B_11") (pintype "input"))
      (node (ref "IC5") (pin "6") (pinfunction "ENABLE_A_6") (pintype "input"))
      (node (ref "IC5") (pin "9") (pinfunction "VCC_9") (pintype "power_in"))
      (node (ref "J1") (pin "3") (pinfunction "3_3") (pintype "passive"))
      (node (ref "J2") (pin "1") (pinfunction "1_1") (pintype "power_in"))
      (node (ref "J3") (pin "2") (pinfunction "2_2") (pintype "power_in"))
      (node (ref "J5") (pin "3") (pinfunction "3_3") (pintype "passive"))
      (node (ref "J6") (pin "3") (pinfunction "3_3") (pintype "passive"))
      (node (ref "J7") (pin "3") (pinfunction "3_3") (pintype "passive"))
      (node (ref "JP10") (pin "1") (pinfunction "1_1") (pintype "passive"))
      (node (ref "JP6") (pin "1") (pinfunction "1_1") (pintype "passive"))
      (node (ref "JP8") (pin "1") (pinfunction "1_1") (pintype "passive"))
      (node (ref "PS1") (pin "2") (pinfunction "+VIN_2") (pintype "input"))
      (node (ref "PS2") (pin "2") (pinfunction "+VIN_2") (pintype "input"))
      (node (ref "PS3") (pin "2") (pinfunction "+VIN_2") (pintype "input"))
      (node (ref "PS4") (pin "2") (pinfunction "+VIN_2") (pintype "input"))
      (node (ref "R12") (pin "6") (pinfunction "2_6") (pintype "passive"))
      (node (ref "R12") (pin "7") (pinfunction "2_7") (pintype "passive"))
      (node (ref "R13") (pin "6") (pinfunction "2_6") (pintype "passive"))
      (node (ref "R13") (pin "7") (pinfunction "2_7") (pintype "passive"))
      (node (ref "R17") (pin "6") (pinfunction "2_6") (pintype "passive"))
      (node (ref "R17") (pin "7") (pinfunction "2_7") (pintype "passive"))
      (node (ref "R2") (pin "2") (pinfunction "2_2") (pintype "passive"))
      (node (ref "R20") (pin "6") (pinfunction "2_6") (pintype "passive"))
      (node (ref "R20") (pin "7") (pinfunction "2_7") (pintype "passive"))
      (node (ref "X10") (pin "1") (pinfunction "VCC1_1") (pintype "power_in"))
      (node (ref "X12") (pin "1") (pinfunction "VCC1_1") (pintype "power_in"))
      (node (ref "X13") (pin "4") (pinfunction "4_4") (pintype "passive"))
      (node (ref "X15") (pin "1") (pinfunction "VCC1_1") (pintype "power_in"))
      (node (ref "X16") (pin "4") (pinfunction "4_4") (pintype "passive"))
      (node (ref "X22") (pin "2") (pinfunction "S_2") (pintype "passive"))
      (node (ref "X8") (pin "1") (pinfunction "VCC1_1") (pintype "power_in"))
      (node (ref "X9") (pin "4") (pinfunction "4_4") (pintype "passive"))
    )
    (net (code "2") (name "+12V") (class "Default")
      (node (ref "C1") (pin "+") (pinfunction "+_+") (pintype "passive"))
      (node (ref "C2") (pin "2") (pinfunction "2_2") (pintype "passive"))
      (node (ref "C6") (pin "2") (pinfunction "2_2") (pintype "passive"))
      (node (ref "C7") (pin "+") (pinfunction "+_+") (pintype "passive"))
      (node (ref "C9") (pin "+") (pinfunction "+_+") (pintype "passive"))
      (node (ref "D12") (pin "C") (pinfunction "C_C") (pintype "passive"))
      (node (ref "D13") (pin "C") (pinfunction "C_C") (pintype "passive"))
      (node (ref "D14") (pin "C") (pinfunction "C_C") (pintype "passive"))
      (node (ref "D15") (pin "C") (pinfunction "C_C") (pintype "passive"))
      (node (ref "D16") (pin "C") (pinfunction "C_C") (pintype "passive"))
      (node (ref "D2") (pin "C") (pinfunction "C_C") (pintype "passive"))
      (node (ref "D21") (pin "C") (pinfunction "C_C") (pintype "passive"))
      (node (ref "D23") (pin "C") (pinfunction "C_C") (pintype "passive"))
      (node (ref "D25") (pin "C") (pinfunction "C_C") (pintype "passive"))
      (node (ref "D27") (pin "C") (pinfunction "C_C") (pintype "passive"))
      (node (ref "D3") (pin "C") (pinfunction "C_C") (pintype "passive"))
      (node (ref "D5") (pin "C") (pinfunction "C_C") (pintype "passive"))
      (node (ref "D7") (pin "C") (pinfunction "C_C") (pintype "passive"))
      (node (ref "D9") (pin "C") (pinfunction "C_C") (pintype "passive"))
      (node (ref "IC1") (pin "3") (pinfunction "IN_3") (pintype "input"))
      (node (ref "IC2") (pin "4") (pinfunction "VS_4") (pintype "power_in"))
      (node (ref "IC3") (pin "3") (pinfunction "IN_3") (pintype "input"))
      (node (ref "IC4") (pin "4") (pinfunction "VS_4") (pintype "power_in"))
      (node (ref "IC5") (pin "4") (pinfunction "VS_4") (pintype "power_in"))
      (node (ref "J8") (pin "PWR") (pinfunction "PWR_PWR") (pintype "bidirectional"))
      (node (ref "U2") (pin "8") (pinfunction "P$V+_8") (pintype "bidirectional"))
      (node (ref "U3") (pin "8") (pinfunction "P$V+_8") (pintype "bidirectional"))
    )
    (net (code "3") (name "/+3.3V") (class "Default")
      (node (ref "C5") (pin "+") (pinfunction "+_+") (pintype "passive"))
      (node (ref "D11") (pin "C") (pinfunction "C_C") (pintype "passive"))
      (node (ref "D12") (pin "A") (pinfunction "A_A") (pintype "passive"))
      (node (ref "IC3") (pin "4") (pinfunction "OUT_4") (pintype "passive"))
      (node (ref "JP1") (pin "3") (pinfunction "3_3") (pintype "passive"))
      (node (ref "JP2") (pin "3") (pinfunction "3_3") (pintype "passive"))
      (node (ref "JP3") (pin "3") (pinfunction "3_3") (pintype "passive"))
      (node (ref "R3") (pin "2") (pinfunction "2_2") (pintype "passive"))
      (node (ref "U1") (pin "18") (pinfunction "~{RESET}_18") (pintype "output"))
      (node (ref "U1") (pin "9") (pinfunction "VDD_9") (pintype "power_in"))
    )
    (net (code "4") (name "/IN-PUMP-1") (class "Default")
      (node (ref "IC2") (pin "5") (pinfunction "INPUT1_5") (pintype "input"))
      (node (ref "U1") (pin "21") (pinfunction "GPA0_21") (pintype "bidirectional"))
    )
    (net (code "5") (name "/IN-PUMP-2") (class "Default")
      (node (ref "IC2") (pin "7") (pinfunction "INPUT2_7") (pintype "input"))
      (node (ref "U1") (pin "22") (pinfunction "GPA1_22") (pintype "bidirectional"))
    )
    (net (code "6") (name "/IN-PUMP-3") (class "Default")
      (node (ref "IC2") (pin "10") (pinfunction "INPUT3_10") (pintype "input"))
      (node (ref "U1") (pin "23") (pinfunction "GPA2_23") (pintype "bidirectional"))
    )
    (net (code "7") (name "/IN-PUMP-4") (class "Default")
      (node (ref "IC2") (pin "12") (pinfunction "INPUT4_12") (pintype "input"))
      (node (ref "U1") (pin "24") (pinfunction "GPA3_24") (pintype "bidirectional"))
    )
    (net (code "8") (name "/IN-PUMP-5") (class "Default")
      (node (ref "IC4") (pin "5") (pinfunction "INPUT1_5") (pintype "input"))
      (node (ref "U1") (pin "25") (pinfunction "GPA4_25") (pintype "bidirectional"))
    )
    (net (code "9") (name "/IN-PUMP-6") (class "Default")
      (node (ref "IC4") (pin "7") (pinfunction "INPUT2_7") (pintype "input"))
      (node (ref "U1") (pin "26") (pinfunction "GPA5_26") (pintype "bidirectional"))
    )
    (net (code "10") (name "/IN-PUMP-7") (class "Default")
      (node (ref "IC4") (pin "10") (pinfunction "INPUT3_10") (pintype "input"))
      (node (ref "U1") (pin "27") (pinfunction "GPA6_27") (pintype "bidirectional"))
    )
    (net (code "11") (name "/IN-PUMP-8") (class "Default")
      (node (ref "IC4") (pin "12") (pinfunction "INPUT4_12") (pintype "input"))
      (node (ref "U1") (pin "28") (pinfunction "GPA7_28") (pintype "bidirectional"))
    )
    (net (code "12") (name "/IN-PUMP-9") (class "Default")
      (node (ref "IC5") (pin "5") (pinfunction "INPUT1_5") (pintype "input"))
      (node (ref "U1") (pin "1") (pinfunction "GPB0_1") (pintype "bidirectional"))
    )
    (net (code "13") (name "/IN-PUMP-10") (class "Default")
      (node (ref "IC5") (pin "7") (pinfunction "INPUT2_7") (pintype "input"))
      (node (ref "U1") (pin "2") (pinfunction "GPB1_2") (pintype "bidirectional"))
    )
    (net (code "14") (name "/IN-PUMP-11") (class "Default")
      (node (ref "IC5") (pin "10") (pinfunction "INPUT3_10") (pintype "input"))
      (node (ref "U1") (pin "3") (pinfunction "GPB2_3") (pintype "bidirectional"))
    )
    (net (code "15") (name "/IN-PUMP-12") (class "Default")
      (node (ref "IC5") (pin "12") (pinfunction "INPUT4_12") (pintype "input"))
      (node (ref "U1") (pin "4") (pinfunction "GPB3_4") (pintype "bidirectional"))
    )
    (net (code "16") (name "/IN-PWM-1") (class "Default")
      (node (ref "JP4") (pin "7") (pinfunction "7_7") (pintype "passive"))
      (node (ref "R1A1") (pin "2") (pinfunction "2_2") (pintype "passive"))
      (node (ref "R5A1") (pin "1") (pinfunction "1_1") (pintype "passive"))
      (node (ref "X1") (pin "1") (pinfunction "S_1") (pintype "passive"))
    )
    (net (code "17") (name "/IN-PWM-2") (class "Default")
      (node (ref "JP4") (pin "5") (pinfunction "5_5") (pintype "passive"))
      (node (ref "R1B1") (pin "1") (pinfunction "1_1") (pintype "passive"))
      (node (ref "R5B1") (pin "1") (pinfunction "1_1") (pintype "passive"))
      (node (ref "X1") (pin "2") (pinfunction "S_2") (pintype "passive"))
    )
    (net (code "18") (name "/IN-PWM-3") (class "Default")
      (node (ref "JP4") (pin "3") (pinfunction "3_3") (pintype "passive"))
      (node (ref "R1A2") (pin "2") (pinfunction "2_2") (pintype "passive"))
      (node (ref "R5A2") (pin "1") (pinfunction "1_1") (pintype "passive"))
      (node (ref "X2") (pin "1") (pinfunction "S_1") (pintype "passive"))
    )
    (net (code "19") (name "/IN-PWM-4") (class "Default")
      (node (ref "JP4") (pin "1") (pinfunction "1_1") (pintype "passive"))
      (node (ref "R1B2") (pin "1") (pinfunction "1_1") (pintype "passive"))
      (node (ref "R5B2") (pin "1") (pinfunction "1_1") (pintype "passive"))
      (node (ref "X2") (pin "2") (pinfunction "S_2") (pintype "passive"))
    )
    (net (code "20") (name "/ISO-1-5V") (class "Default")
      (node (ref "C11") (pin "1") (pinfunction "1_1") (pintype "passive"))
      (node (ref "JP13") (pin "1") (pinfunction "1_1") (pintype "passive"))
      (node (ref "PS1") (pin "4") (pinfunction "+VOUT_4") (pintype "output"))
      (node (ref "R14") (pin "6") (pinfunction "2_6") (pintype "passive"))
      (node (ref "R14") (pin "7") (pinfunction "2_7") (pintype "passive"))
      (node (ref "X8") (pin "8") (pinfunction "VCC2_8") (pintype "power_in"))
    )
    (net (code "21") (name "/ISO-2-5V") (class "Default")
      (node (ref "C13") (pin "1") (pinfunction "1_1") (pintype "passive"))
      (node (ref "JP15") (pin "1") (pinfunction "1_1") (pintype "passive"))
      (node (ref "PS2") (pin "4") (pinfunction "+VOUT_4") (pintype "output"))
      (node (ref "R16") (pin "6") (pinfunction "2_6") (pintype "passive"))
      (node (ref "R16") (pin "7") (pinfunction "2_7") (pintype "passive"))
      (node (ref "X10") (pin "8") (pinfunction "VCC2_8") (pintype "power_in"))
    )
    (net (code "22") (name "/ISO-3-5V") (class "Default")
      (node (ref "C15") (pin "1") (pinfunction "1_1") (pintype "passive"))
      (node (ref "JP17") (pin "1") (pinfunction "1_1") (pintype "passive"))
      (node (ref "PS3") (pin "4") (pinfunction "+VOUT_4") (pintype "output"))
      (node (ref "R18") (pin "6") (pinfunction "2_6") (pintype "passive"))
      (node (ref "R18") (pin "7") (pinfunction "2_7") (pintype "passive"))
      (node (ref "X12") (pin "8") (pinfunction "VCC2_8") (pintype "power_in"))
    )
    (net (code "23") (name "/ISO-4-5V") (class "Default")
      (node (ref "C17") (pin "1") (pinfunction "1_1") (pintype "passive"))
      (node (ref "JP19") (pin "1") (pinfunction "1_1") (pintype "passive"))
      (node (ref "PS4") (pin "4") (pinfunction "+VOUT_4") (pintype "output"))
      (node (ref "R21") (pin "6") (pinfunction "2_6") (pintype "passive"))
      (node (ref "R21") (pin "7") (pinfunction "2_7") (pintype "passive"))
      (node (ref "X15") (pin "8") (pinfunction "VCC2_8") (pintype "power_in"))
    )
    (net (code "24") (name "/ISO-GND-1") (class "Default")
      (node (ref "C11") (pin "2") (pinfunction "2_2") (pintype "passive"))
      (node (ref "JP12") (pin "3") (pinfunction "3_3") (pintype "passive"))
      (node (ref "PS1") (pin "3") (pinfunction "-VOUT_3") (pintype "output"))
      (node (ref "X8") (pin "5") (pinfunction "GND2_5") (pintype "power_in"))
    )
    (net (code "25") (name "/ISO-GND-2") (class "Default")
      (node (ref "C13") (pin "2") (pinfunction "2_2") (pintype "passive"))
      (node (ref "JP14") (pin "3") (pinfunction "3_3") (pintype "passive"))
      (node (ref "PS2") (pin "3") (pinfunction "-VOUT_3") (pintype "output"))
      (node (ref "X10") (pin "5") (pinfunction "GND2_5") (pintype "power_in"))
    )
    (net (code "26") (name "/ISO-GND-3") (class "Default")
      (node (ref "C15") (pin "2") (pinfunction "2_2") (pintype "passive"))
      (node (ref "JP16") (pin "3") (pinfunction "3_3") (pintype "passive"))
      (node (ref "PS3") (pin "3") (pinfunction "-VOUT_3") (pintype "output"))
      (node (ref "X12") (pin "5") (pinfunction "GND2_5") (pintype "power_in"))
    )
    (net (code "27") (name "/ISO-GND-4") (class "Default")
      (node (ref "C17") (pin "2") (pinfunction "2_2") (pintype "passive"))
      (node (ref "JP18") (pin "3") (pinfunction "3_3") (pintype "passive"))
      (node (ref "PS4") (pin "3") (pinfunction "-VOUT_3") (pintype "output"))
      (node (ref "X15") (pin "5") (pinfunction "GND2_5") (pintype "power_in"))
    )
    (net (code "28") (name "/LED1") (class "Default")
      (node (ref "JP4") (pin "2") (pinfunction "2_2") (pintype "passive"))
      (node (ref "R7") (pin "1") (pinfunction "1_1") (pintype "passive"))
      (node (ref "U1") (pin "5") (pinfunction "GPB4_5") (pintype "bidirectional"))
    )
    (net (code "29") (name "/LED2") (class "Default")
      (node (ref "JP4") (pin "4") (pinfunction "4_4") (pintype "passive"))
      (node (ref "R7") (pin "2") (pinfunction "1_2") (pintype "passive"))
      (node (ref "U1") (pin "6") (pinfunction "GPB5_6") (pintype "bidirectional"))
    )
    (net (code "30") (name "/LED3") (class "Default")
      (node (ref "JP4") (pin "6") (pinfunction "6_6") (pintype "passive"))
      (node (ref "R7") (pin "3") (pinfunction "1_3") (pintype "passive"))
      (node (ref "U1") (pin "7") (pinfunction "GPB6_7") (pintype "bidirectional"))
    )
    (net (code "31") (name "/LED4") (class "Default")
      (node (ref "JP4") (pin "8") (pinfunction "8_8") (pintype "passive"))
      (node (ref "R7") (pin "4") (pinfunction "1_4") (pintype "passive"))
      (node (ref "U1") (pin "8") (pinfunction "GPB7_8") (pintype "bidirectional"))
    )
    (net (code "32") (name "/SCL") (class "Default")
      (node (ref "J1") (pin "1") (pinfunction "1_1") (pintype "power_in"))
      (node (ref "J2") (pin "3") (pinfunction "3_3") (pintype "passive"))
      (node (ref "J3") (pin "3") (pinfunction "3_3") (pintype "passive"))
      (node (ref "J5") (pin "1") (pinfunction "1_1") (pintype "power_in"))
      (node (ref "J6") (pin "1") (pinfunction "1_1") (pintype "power_in"))
      (node (ref "J7") (pin "1") (pinfunction "1_1") (pintype "power_in"))
      (node (ref "JP5") (pin "1") (pinfunction "1_1") (pintype "passive"))
      (node (ref "JP7") (pin "1") (pinfunction "1_1") (pintype "passive"))
      (node (ref "JP9") (pin "1") (pinfunction "1_1") (pintype "passive"))
      (node (ref "R12") (pin "3") (pinfunction "1_3") (pintype "passive"))
      (node (ref "R13") (pin "3") (pinfunction "1_3") (pintype "passive"))
      (node (ref "R17") (pin "3") (pinfunction "1_3") (pintype "passive"))
      (node (ref "R20") (pin "3") (pinfunction "1_3") (pintype "passive"))
      (node (ref "U1") (pin "12") (pinfunction "SCK_12") (pintype "input"))
      (node (ref "X10") (pin "3") (pinfunction "SCL1_3") (pintype "bidirectional"))
      (node (ref "X12") (pin "3") (pinfunction "SCL1_3") (pintype "bidirectional"))
      (node (ref "X13") (pin "8") (pinfunction "8_8") (pintype "passive"))
      (node (ref "X15") (pin "3") (pinfunction "SCL1_3") (pintype "bidirectional"))
      (node (ref "X16") (pin "8") (pinfunction "8_8") (pintype "passive"))
      (node (ref "X3") (pin "1") (pinfunction "S_1") (pintype "passive"))
      (node (ref "X8") (pin "3") (pinfunction "SCL1_3") (pintype "bidirectional"))
      (node (ref "X9") (pin "8") (pinfunction "8_8") (pintype "passive"))
    )
    (net (code "33") (name "/SCL2") (class "Default")
      (node (ref "JP12") (pin "1") (pinfunction "1_1") (pintype "passive"))
      (node (ref "R14") (pin "3") (pinfunction "1_3") (pintype "passive"))
      (node (ref "X8") (pin "6") (pinfunction "SCL2_6") (pintype "bidirectional"))
    )
    (net (code "34") (name "/SCL3") (class "Default")
      (node (ref "JP14") (pin "1") (pinfunction "1_1") (pintype "passive"))
      (node (ref "R16") (pin "3") (pinfunction "1_3") (pintype "passive"))
      (node (ref "X10") (pin "6") (pinfunction "SCL2_6") (pintype "bidirectional"))
    )
    (net (code "35") (name "/SCL4") (class "Default")
      (node (ref "JP16") (pin "1") (pinfunction "1_1") (pintype "passive"))
      (node (ref "R18") (pin "3") (pinfunction "1_3") (pintype "passive"))
      (node (ref "X12") (pin "6") (pinfunction "SCL2_6") (pintype "bidirectional"))
    )
    (net (code "36") (name "/SCL5") (class "Default")
      (node (ref "JP18") (pin "1") (pinfunction "1_1") (pintype "passive"))
      (node (ref "R21") (pin "3") (pinfunction "1_3") (pintype "passive"))
      (node (ref "X15") (pin "6") (pinfunction "SCL2_6") (pintype "bidirectional"))
    )
    (net (code "37") (name "/SDA") (class "Default")
      (node (ref "J1") (pin "2") (pinfunction "2_2") (pintype "power_in"))
      (node (ref "J2") (pin "4") (pinfunction "4_4") (pintype "passive"))
      (node (ref "J3") (pin "4") (pinfunction "4_4") (pintype "passive"))
      (node (ref "J5") (pin "2") (pinfunction "2_2") (pintype "power_in"))
      (node (ref "J6") (pin "2") (pinfunction "2_2") (pintype "power_in"))
      (node (ref "J7") (pin "2") (pinfunction "2_2") (pintype "power_in"))
      (node (ref "JP5") (pin "2") (pinfunction "2_2") (pintype "passive"))
      (node (ref "JP7") (pin "2") (pinfunction "2_2") (pintype "passive"))
      (node (ref "JP9") (pin "2") (pinfunction "2_2") (pintype "passive"))
      (node (ref "R12") (pin "2") (pinfunction "1_2") (pintype "passive"))
      (node (ref "R13") (pin "2") (pinfunction "1_2") (pintype "passive"))
      (node (ref "R17") (pin "2") (pinfunction "1_2") (pintype "passive"))
      (node (ref "R20") (pin "2") (pinfunction "1_2") (pintype "passive"))
      (node (ref "U1") (pin "13") (pinfunction "SDA_13") (pintype "bidirectional"))
      (node (ref "X10") (pin "2") (pinfunction "SDA1_2") (pintype "bidirectional"))
      (node (ref "X12") (pin "2") (pinfunction "SDA1_2") (pintype "bidirectional"))
      (node (ref "X13") (pin "6") (pinfunction "6_6") (pintype "passive"))
      (node (ref "X15") (pin "2") (pinfunction "SDA1_2") (pintype "bidirectional"))
      (node (ref "X16") (pin "6") (pinfunction "6_6") (pintype "passive"))
      (node (ref "X3") (pin "2") (pinfunction "S_2") (pintype "passive"))
      (node (ref "X8") (pin "2") (pinfunction "SDA1_2") (pintype "bidirectional"))
      (node (ref "X9") (pin "6") (pinfunction "6_6") (pintype "passive"))
    )
    (net (code "38") (name "/SDA2") (class "Default")
      (node (ref "JP12") (pin "2") (pinfunction "2_2") (pintype "passive"))
      (node (ref "R14") (pin "2") (pinfunction "1_2") (pintype "passive"))
      (node (ref "X8") (pin "7") (pinfunction "SDA2_7") (pintype "bidirectional"))
    )
    (net (code "39") (name "/SDA3") (class "Default")
      (node (ref "JP14") (pin "2") (pinfunction "2_2") (pintype "passive"))
      (node (ref "R16") (pin "2") (pinfunction "1_2") (pintype "passive"))
      (node (ref "X10") (pin "7") (pinfunction "SDA2_7") (pintype "bidirectional"))
    )
    (net (code "40") (name "/SDA4") (class "Default")
      (node (ref "JP16") (pin "2") (pinfunction "2_2") (pintype "passive"))
      (node (ref "R18") (pin "2") (pinfunction "1_2") (pintype "passive"))
      (node (ref "X12") (pin "7") (pinfunction "SDA2_7") (pintype "bidirectional"))
    )
    (net (code "41") (name "/SDA5") (class "Default")
      (node (ref "JP18") (pin "2") (pinfunction "2_2") (pintype "passive"))
      (node (ref "R21") (pin "2") (pinfunction "1_2") (pintype "passive"))
      (node (ref "X15") (pin "7") (pinfunction "SDA2_7") (pintype "bidirectional"))
    )
    (net (code "42") (name "GND") (class "Default")
      (node (ref "C1") (pin "-") (pinfunction "-_-") (pintype "passive"))
      (node (ref "C10") (pin "2") (pinfunction "2_2") (pintype "passive"))
      (node (ref "C12") (pin "2") (pinfunction "2_2") (pintype "passive"))
      (node (ref "C14") (pin "2") (pinfunction "2_2") (pintype "passive"))
      (node (ref "C16") (pin "2") (pinfunction "2_2") (pintype "passive"))
      (node (ref "C1A1") (pin "-") (pinfunction "-_-") (pintype "passive"))
      (node (ref "C1A2") (pin "-") (pinfunction "-_-") (pintype "passive"))
      (node (ref "C1B1") (pin "-") (pinfunction "-_-") (pintype "passive"))
      (node (ref "C1B2") (pin "-") (pinfunction "-_-") (pintype "passive"))
      (node (ref "C2") (pin "1") (pinfunction "1_1") (pintype "passive"))
      (node (ref "C3") (pin "-") (pinfunction "-_-") (pintype "passive"))
      (node (ref "C4") (pin "-") (pinfunction "-_-") (pintype "passive"))
      (node (ref "C5") (pin "-") (pinfunction "-_-") (pintype "passive"))
      (node (ref "C6") (pin "1") (pinfunction "1_1") (pintype "passive"))
      (node (ref "C7") (pin "-") (pinfunction "-_-") (pintype "passive"))
      (node (ref "C8") (pin "-") (pinfunction "-_-") (pintype "passive"))
      (node (ref "C9") (pin "-") (pinfunction "-_-") (pintype "passive"))
      (node (ref "D10") (pin "A") (pinfunction "A_A") (pintype "passive"))
      (node (ref "D17") (pin "A") (pinfunction "A_A") (pintype "passive"))
      (node (ref "D18") (pin "A") (pinfunction "A_A") (pintype "passive"))
      (node (ref "D19") (pin "A") (pinfunction "A_A") (pintype "passive"))
      (node (ref "D20") (pin "A") (pinfunction "A_A") (pintype "passive"))
      (node (ref "D22") (pin "A") (pinfunction "A_A") (pintype "passive"))
      (node (ref "D24") (pin "A") (pinfunction "A_A") (pintype "passive"))
      (node (ref "D26") (pin "A") (pinfunction "A_A") (pintype "passive"))
      (node (ref "D28") (pin "A") (pinfunction "A_A") (pintype "passive"))
      (node (ref "D4") (pin "A") (pinfunction "A_A") (pintype "passive"))
      (node (ref "D6") (pin "A") (pinfunction "A_A") (pintype "passive"))
      (node (ref "D8") (pin "A") (pinfunction "A_A") (pintype "passive"))
      (node (ref "IC2") (pin "8") (pinfunction "GND_8") (pintype "power_in"))
      (node (ref "IC4") (pin "8") (pinfunction "GND_8") (pintype "power_in"))
      (node (ref "IC5") (pin "8") (pinfunction "GND_8") (pintype "power_in"))
      (node (ref "J1") (pin "4") (pinfunction "4_4") (pintype "passive"))
      (node (ref "J2") (pin "2") (pinfunction "2_2") (pintype "power_in"))
      (node (ref "J3") (pin "1") (pinfunction "1_1") (pintype "power_in"))
      (node (ref "J5") (pin "4") (pinfunction "4_4") (pintype "passive"))
      (node (ref "J6") (pin "4") (pinfunction "4_4") (pintype "passive"))
      (node (ref "J7") (pin "4") (pinfunction "4_4") (pintype "passive"))
      (node (ref "J8") (pin "GND") (pinfunction "GND_GND") (pintype "bidirectional"))
      (node (ref "J8") (pin "GNDBREAK") (pinfunction "GNDBREAK_GNDBREAK") (pintype "bidirectional"))
      (node (ref "JP1") (pin "1") (pinfunction "1_1") (pintype "passive"))
      (node (ref "JP2") (pin "1") (pinfunction "1_1") (pintype "passive"))
      (node (ref "JP3") (pin "1") (pinfunction "1_1") (pintype "passive"))
      (node (ref "JP5") (pin "3") (pinfunction "3_3") (pintype "passive"))
      (node (ref "JP7") (pin "3") (pinfunction "3_3") (pintype "passive"))
      (node (ref "JP9") (pin "3") (pinfunction "3_3") (pintype "passive"))
      (node (ref "LED1") (pin "C") (pinfunction "C_C") (pintype "passive"))
      (node (ref "LED10") (pin "C") (pinfunction "C_C") (pintype "passive"))
      (node (ref "LED11") (pin "C") (pinfunction "C_C") (pintype "passive"))
      (node (ref "LED12") (pin "C") (pinfunction "C_C") (pintype "passive"))
      (node (ref "LED13") (pin "C") (pinfunction "C_C") (pintype "passive"))
      (node (ref "LED14") (pin "C") (pinfunction "C_C") (pintype "passive"))
      (node (ref "LED15") (pin "C") (pinfunction "C_C") (pintype "passive"))
      (node (ref "LED16") (pin "C") (pinfunction "C_C") (pintype "passive"))
      (node (ref "LED2") (pin "C") (pinfunction "C_C") (pintype "passive"))
      (node (ref "LED3") (pin "C") (pinfunction "C_C") (pintype "passive"))
      (node (ref "LED4") (pin "C") (pinfunction "C_C") (pintype "passive"))
      (node (ref "LED5") (pin "C") (pinfunction "C_C") (pintype "passive"))
      (node (ref "LED6") (pin "C") (pinfunction "C_C") (pintype "passive"))
      (node (ref "LED7") (pin "C") (pinfunction "C_C") (pintype "passive"))
      (node (ref "LED8") (pin "C") (pinfunction "C_C") (pintype "passive"))
      (node (ref "LED9") (pin "C") (pinfunction "C_C") (pintype "passive"))
      (node (ref "PS1") (pin "1") (pinfunction "-VIN_1") (pintype "input"))
      (node (ref "PS2") (pin "1") (pinfunction "-VIN_1") (pintype "input"))
      (node (ref "PS3") (pin "1") (pinfunction "-VIN_1") (pintype "input"))
      (node (ref "PS4") (pin "1") (pinfunction "-VIN_1") (pintype "input"))
      (node (ref "R1") (pin "1") (pinfunction "1_1") (pintype "passive"))
      (node (ref "R10") (pin "1") (pinfunction "1_1") (pintype "passive"))
      (node (ref "R11") (pin "1") (pinfunction "1_1") (pintype "passive"))
      (node (ref "R2A1") (pin "1") (pinfunction "1_1") (pintype "passive"))
      (node (ref "R2A2") (pin "1") (pinfunction "1_1") (pintype "passive"))
      (node (ref "R2B1") (pin "2") (pinfunction "2_2") (pintype "passive"))
      (node (ref "R2B2") (pin "2") (pinfunction "2_2") (pintype "passive"))
      (node (ref "R4") (pin "1") (pinfunction "1_1") (pintype "passive"))
      (node (ref "R5") (pin "1") (pinfunction "1_1") (pintype "passive"))
      (node (ref "R5A1") (pin "2") (pinfunction "2_2") (pintype "passive"))
      (node (ref "R5A2") (pin "2") (pinfunction "2_2") (pintype "passive"))
      (node (ref "R5B1") (pin "2") (pinfunction "2_2") (pintype "passive"))
      (node (ref "R5B2") (pin "2") (pinfunction "2_2") (pintype "passive"))
      (node (ref "R6") (pin "1") (pinfunction "1_1") (pintype "passive"))
      (node (ref "R8") (pin "1") (pinfunction "1_1") (pintype "passive"))
      (node (ref "R9") (pin "1") (pinfunction "1_1") (pintype "passive"))
      (node (ref "U1") (pin "10") (pinfunction "VSS_10") (pintype "power_in"))
      (node (ref "U2") (pin "4") (pinfunction "P$V-_4") (pintype "bidirectional"))
      (node (ref "U3") (pin "4") (pinfunction "P$V-_4") (pintype "bidirectional"))
      (node (ref "X10") (pin "4") (pinfunction "GND1_4") (pintype "power_in"))
      (node (ref "X12") (pin "4") (pinfunction "GND1_4") (pintype "power_in"))
      (node (ref "X13") (pin "2") (pinfunction "2_2") (pintype "passive"))
      (node (ref "X15") (pin "4") (pinfunction "GND1_4") (pintype "power_in"))
      (node (ref "X16") (pin "2") (pinfunction "2_2") (pintype "passive"))
      (node (ref "X22") (pin "1") (pinfunction "S_1") (pintype "passive"))
      (node (ref "X4") (pin "2") (pinfunction "S_2") (pintype "passive"))
      (node (ref "X5") (pin "2") (pinfunction "S_2") (pintype "passive"))
      (node (ref "X6") (pin "2") (pinfunction "S_2") (pintype "passive"))
      (node (ref "X7") (pin "2") (pinfunction "S_2") (pintype "passive"))
      (node (ref "X8") (pin "4") (pinfunction "GND1_4") (pintype "power_in"))
      (node (ref "X9") (pin "2") (pinfunction "2_2") (pintype "passive"))
    )
    (net (code "43") (name "Net-(C1A1-Pad+)") (class "Default")
      (node (ref "C1A1") (pin "+") (pinfunction "+_+") (pintype "passive"))
      (node (ref "R1A1") (pin "1") (pinfunction "1_1") (pintype "passive"))
      (node (ref "R4A2") (pin "1") (pinfunction "1_1") (pintype "passive"))
    )
    (net (code "44") (name "Net-(C1A2-Pad+)") (class "Default")
      (node (ref "C1A2") (pin "+") (pinfunction "+_+") (pintype "passive"))
      (node (ref "R1A2") (pin "1") (pinfunction "1_1") (pintype "passive"))
      (node (ref "R4A1") (pin "1") (pinfunction "1_1") (pintype "passive"))
    )
    (net (code "45") (name "Net-(C1B1-Pad+)") (class "Default")
      (node (ref "C1B1") (pin "+") (pinfunction "+_+") (pintype "passive"))
      (node (ref "R1B1") (pin "2") (pinfunction "2_2") (pintype "passive"))
      (node (ref "R4B1") (pin "1") (pinfunction "1_1") (pintype "passive"))
    )
    (net (code "46") (name "Net-(C1B2-Pad+)") (class "Default")
      (node (ref "C1B2") (pin "+") (pinfunction "+_+") (pintype "passive"))
      (node (ref "R1B2") (pin "2") (pinfunction "2_2") (pintype "passive"))
      (node (ref "R4B2") (pin "1") (pinfunction "1_1") (pintype "passive"))
    )
    (net (code "47") (name "Net-(IC1-ADJ)") (class "Default")
      (node (ref "C4") (pin "+") (pinfunction "+_+") (pintype "passive"))
      (node (ref "D1") (pin "A") (pinfunction "A_A") (pintype "passive"))
      (node (ref "IC1") (pin "1") (pinfunction "ADJ_1") (pintype "input"))
      (node (ref "R2") (pin "1") (pinfunction "1_1") (pintype "passive"))
      (node (ref "R4") (pin "2") (pinfunction "2_2") (pintype "passive"))
    )
    (net (code "48") (name "Net-(IC2-OUT1)") (class "Default")
      (node (ref "D3") (pin "A") (pinfunction "A_A") (pintype "passive"))
      (node (ref "D4") (pin "C") (pinfunction "C_C") (pintype "passive"))
      (node (ref "IC2") (pin "2") (pinfunction "OUT1_2") (pintype "output"))
      (node (ref "R15") (pin "1") (pinfunction "1_1") (pintype "passive"))
      (node (ref "X9") (pin "1") (pinfunction "1_1") (pintype "passive"))
    )
    (net (code "49") (name "Net-(IC2-OUT2)") (class "Default")
      (node (ref "D5") (pin "A") (pinfunction "A_A") (pintype "passive"))
      (node (ref "D6") (pin "C") (pinfunction "C_C") (pintype "passive"))
      (node (ref "IC2") (pin "3") (pinfunction "OUT2_3") (pintype "output"))
      (node (ref "R15") (pin "2") (pinfunction "1_2") (pintype "passive"))
      (node (ref "X9") (pin "3") (pinfunction "3_3") (pintype "passive"))
    )
    (net (code "50") (name "Net-(IC2-OUT3)") (class "Default")
      (node (ref "D7") (pin "A") (pinfunction "A_A") (pintype "passive"))
      (node (ref "D8") (pin "C") (pinfunction "C_C") (pintype "passive"))
      (node (ref "IC2") (pin "13") (pinfunction "OUT3_13") (pintype "output"))
      (node (ref "R15") (pin "3") (pinfunction "1_3") (pintype "passive"))
      (node (ref "X9") (pin "5") (pinfunction "5_5") (pintype "passive"))
    )
    (net (code "51") (name "Net-(IC2-OUT4)") (class "Default")
      (node (ref "D10") (pin "C") (pinfunction "C_C") (pintype "passive"))
      (node (ref "D9") (pin "A") (pinfunction "A_A") (pintype "passive"))
      (node (ref "IC2") (pin "14") (pinfunction "OUT4_14") (pintype "output"))
      (node (ref "R15") (pin "4") (pinfunction "1_4") (pintype "passive"))
      (node (ref "X9") (pin "7") (pinfunction "7_7") (pintype "passive"))
    )
    (net (code "52") (name "Net-(IC2-SEN_A)") (class "Default")
      (node (ref "IC2") (pin "1") (pinfunction "SEN_A_1") (pintype "input"))
      (node (ref "R1") (pin "2") (pinfunction "2_2") (pintype "passive"))
    )
    (net (code "53") (name "Net-(IC2-SEN_B)") (class "Default")
      (node (ref "IC2") (pin "15") (pinfunction "SEN_B_15") (pintype "input"))
      (node (ref "R6") (pin "2") (pinfunction "2_2") (pintype "passive"))
    )
    (net (code "54") (name "Net-(IC3-ADJ)") (class "Default")
      (node (ref "C8") (pin "+") (pinfunction "+_+") (pintype "passive"))
      (node (ref "D11") (pin "A") (pinfunction "A_A") (pintype "passive"))
      (node (ref "IC3") (pin "1") (pinfunction "ADJ_1") (pintype "input"))
      (node (ref "R3") (pin "1") (pinfunction "1_1") (pintype "passive"))
      (node (ref "R5") (pin "2") (pinfunction "2_2") (pintype "passive"))
    )
    (net (code "55") (name "Net-(IC4-OUT1)") (class "Default")
      (node (ref "D13") (pin "A") (pinfunction "A_A") (pintype "passive"))
      (node (ref "D17") (pin "C") (pinfunction "C_C") (pintype "passive"))
      (node (ref "IC4") (pin "2") (pinfunction "OUT1_2") (pintype "output"))
      (node (ref "R19") (pin "1") (pinfunction "1_1") (pintype "passive"))
      (node (ref "X13") (pin "1") (pinfunction "1_1") (pintype "passive"))
    )
    (net (code "56") (name "Net-(IC4-OUT2)") (class "Default")
      (node (ref "D14") (pin "A") (pinfunction "A_A") (pintype "passive"))
      (node (ref "D18") (pin "C") (pinfunction "C_C") (pintype "passive"))
      (node (ref "IC4") (pin "3") (pinfunction "OUT2_3") (pintype "output"))
      (node (ref "R19") (pin "2") (pinfunction "1_2") (pintype "passive"))
      (node (ref "X13") (pin "3") (pinfunction "3_3") (pintype "passive"))
    )
    (net (code "57") (name "Net-(IC4-OUT3)") (class "Default")
      (node (ref "D15") (pin "A") (pinfunction "A_A") (pintype "passive"))
      (node (ref "D19") (pin "C") (pinfunction "C_C") (pintype "passive"))
      (node (ref "IC4") (pin "13") (pinfunction "OUT3_13") (pintype "output"))
      (node (ref "R19") (pin "3") (pinfunction "1_3") (pintype "passive"))
      (node (ref "X13") (pin "5") (pinfunction "5_5") (pintype "passive"))
    )
    (net (code "58") (name "Net-(IC4-OUT4)") (class "Default")
      (node (ref "D16") (pin "A") (pinfunction "A_A") (pintype "passive"))
      (node (ref "D20") (pin "C") (pinfunction "C_C") (pintype "passive"))
      (node (ref "IC4") (pin "14") (pinfunction "OUT4_14") (pintype "output"))
      (node (ref "R19") (pin "4") (pinfunction "1_4") (pintype "passive"))
      (node (ref "X13") (pin "7") (pinfunction "7_7") (pintype "passive"))
    )
    (net (code "59") (name "Net-(IC4-SEN_A)") (class "Default")
      (node (ref "IC4") (pin "1") (pinfunction "SEN_A_1") (pintype "input"))
      (node (ref "R9") (pin "2") (pinfunction "2_2") (pintype "passive"))
    )
    (net (code "60") (name "Net-(IC4-SEN_B)") (class "Default")
      (node (ref "IC4") (pin "15") (pinfunction "SEN_B_15") (pintype "input"))
      (node (ref "R8") (pin "2") (pinfunction "2_2") (pintype "passive"))
    )
    (net (code "61") (name "Net-(IC5-OUT1)") (class "Default")
      (node (ref "D21") (pin "A") (pinfunction "A_A") (pintype "passive"))
      (node (ref "D22") (pin "C") (pinfunction "C_C") (pintype "passive"))
      (node (ref "IC5") (pin "2") (pinfunction "OUT1_2") (pintype "output"))
      (node (ref "R22") (pin "1") (pinfunction "1_1") (pintype "passive"))
      (node (ref "X16") (pin "1") (pinfunction "1_1") (pintype "passive"))
    )
    (net (code "62") (name "Net-(IC5-OUT2)") (class "Default")
      (node (ref "D23") (pin "A") (pinfunction "A_A") (pintype "passive"))
      (node (ref "D24") (pin "C") (pinfunction "C_C") (pintype "passive"))
      (node (ref "IC5") (pin "3") (pinfunction "OUT2_3") (pintype "output"))
      (node (ref "R22") (pin "2") (pinfunction "1_2") (pintype "passive"))
      (node (ref "X16") (pin "3") (pinfunction "3_3") (pintype "passive"))
    )
    (net (code "63") (name "Net-(IC5-OUT3)") (class "Default")
      (node (ref "D25") (pin "A") (pinfunction "A_A") (pintype "passive"))
      (node (ref "D26") (pin "C") (pinfunction "C_C") (pintype "passive"))
      (node (ref "IC5") (pin "13") (pinfunction "OUT3_13") (pintype "output"))
      (node (ref "R22") (pin "3") (pinfunction "1_3") (pintype "passive"))
      (node (ref "X16") (pin "5") (pinfunction "5_5") (pintype "passive"))
    )
    (net (code "64") (name "Net-(IC5-OUT4)") (class "Default")
      (node (ref "D27") (pin "A") (pinfunction "A_A") (pintype "passive"))
      (node (ref "D28") (pin "C") (pinfunction "C_C") (pintype "passive"))
      (node (ref "IC5") (pin "14") (pinfunction "OUT4_14") (pintype "output"))
      (node (ref "R22") (pin "4") (pinfunction "1_4") (pintype "passive"))
      (node (ref "X16") (pin "7") (pinfunction "7_7") (pintype "passive"))
    )
    (net (code "65") (name "Net-(IC5-SEN_A)") (class "Default")
      (node (ref "IC5") (pin "1") (pinfunction "SEN_A_1") (pintype "input"))
      (node (ref "R11") (pin "2") (pinfunction "2_2") (pintype "passive"))
    )
    (net (code "66") (name "Net-(IC5-SEN_B)") (class "Default")
      (node (ref "IC5") (pin "15") (pinfunction "SEN_B_15") (pintype "input"))
      (node (ref "R10") (pin "2") (pinfunction "2_2") (pintype "passive"))
    )
    (net (code "67") (name "Net-(JP13-Pad2)") (class "Default")
      (node (ref "JP13") (pin "2") (pinfunction "2_2") (pintype "passive"))
      (node (ref "X18") (pin "1") (pinfunction "1_1") (pintype "passive"))
    )
    (net (code "68") (name "Net-(JP13-Pad3)") (class "Default")
      (node (ref "JP13") (pin "3") (pinfunction "3_3") (pintype "passive"))
      (node (ref "X18") (pin "2") (pinfunction "2_2") (pintype "passive"))
      (node (ref "X18") (pin "3") (pinfunction "2_3") (pintype "passive"))
      (node (ref "X18") (pin "4") (pinfunction "2_4") (pintype "passive"))
      (node (ref "X18") (pin "5") (pinfunction "2_5") (pintype "passive"))
    )
    (net (code "69") (name "Net-(JP15-Pad2)") (class "Default")
      (node (ref "JP15") (pin "2") (pinfunction "2_2") (pintype "passive"))
      (node (ref "X19") (pin "1") (pinfunction "1_1") (pintype "passive"))
    )
    (net (code "70") (name "Net-(JP15-Pad3)") (class "Default")
      (node (ref "JP15") (pin "3") (pinfunction "3_3") (pintype "passive"))
      (node (ref "X19") (pin "2") (pinfunction "2_2") (pintype "passive"))
      (node (ref "X19") (pin "3") (pinfunction "2_3") (pintype "passive"))
      (node (ref "X19") (pin "4") (pinfunction "2_4") (pintype "passive"))
      (node (ref "X19") (pin "5") (pinfunction "2_5") (pintype "passive"))
    )
    (net (code "71") (name "Net-(JP17-Pad2)") (class "Default")
      (node (ref "JP17") (pin "2") (pinfunction "2_2") (pintype "passive"))
      (node (ref "X20") (pin "1") (pinfunction "1_1") (pintype "passive"))
    )
    (net (code "72") (name "Net-(JP17-Pad3)") (class "Default")
      (node (ref "JP17") (pin "3") (pinfunction "3_3") (pintype "passive"))
      (node (ref "X20") (pin "2") (pinfunction "2_2") (pintype "passive"))
      (node (ref "X20") (pin "3") (pinfunction "2_3") (pintype "passive"))
      (node (ref "X20") (pin "4") (pinfunction "2_4") (pintype "passive"))
      (node (ref "X20") (pin "5") (pinfunction "2_5") (pintype "passive"))
    )
    (net (code "73") (name "Net-(JP19-Pad2)") (class "Default")
      (node (ref "JP19") (pin "2") (pinfunction "2_2") (pintype "passive"))
      (node (ref "X21") (pin "1") (pinfunction "1_1") (pintype "passive"))
    )
    (net (code "74") (name "Net-(JP19-Pad3)") (class "Default")
      (node (ref "JP19") (pin "3") (pinfunction "3_3") (pintype "passive"))
      (node (ref "X21") (pin "2") (pinfunction "2_2") (pintype "passive"))
      (node (ref "X21") (pin "3") (pinfunction "2_3") (pintype "passive"))
      (node (ref "X21") (pin "4") (pinfunction "2_4") (pintype "passive"))
      (node (ref "X21") (pin "5") (pinfunction "2_5") (pintype "passive"))
    )
    (net (code "75") (name "Net-(R3-1A1-CCW)") (class "Default")
      (node (ref "R2A1") (pin "2") (pinfunction "2_2") (pintype "passive"))
      (node (ref "R3-1A1") (pin "1") (pinfunction "CCW_1") (pintype "passive"))
      (node (ref "U2") (pin "6") (pinfunction "-IN_6") (pintype "input"))
    )
    (net (code "76") (name "Net-(R3-1A1-CW)") (class "Default")
      (node (ref "R3-1A1") (pin "2") (pinfunction "WIPER_2") (pintype "passive"))
      (node (ref "R3-1A1") (pin "3") (pinfunction "CW_3") (pintype "passive"))
      (node (ref "R3-2A1") (pin "1") (pinfunction "1_1") (pintype "passive"))
    )
    (net (code "77") (name "Net-(R3-1A2-CCW)") (class "Default")
      (node (ref "R2A2") (pin "2") (pinfunction "2_2") (pintype "passive"))
      (node (ref "R3-1A2") (pin "1") (pinfunction "CCW_1") (pintype "passive"))
      (node (ref "U3") (pin "6") (pinfunction "-IN_6") (pintype "input"))
    )
    (net (code "78") (name "Net-(R3-1A2-CW)") (class "Default")
      (node (ref "R3-1A2") (pin "2") (pinfunction "WIPER_2") (pintype "passive"))
      (node (ref "R3-1A2") (pin "3") (pinfunction "CW_3") (pintype "passive"))
      (node (ref "R3-2A2") (pin "1") (pinfunction "1_1") (pintype "passive"))
    )
    (net (code "79") (name "Net-(R3-1B1-CCW)") (class "Default")
      (node (ref "R2B1") (pin "1") (pinfunction "1_1") (pintype "passive"))
      (node (ref "R3-1B1") (pin "1") (pinfunction "CCW_1") (pintype "passive"))
      (node (ref "U2") (pin "2") (pinfunction "-IN_2") (pintype "input"))
    )
    (net (code "80") (name "Net-(R3-1B1-CW)") (class "Default")
      (node (ref "R3-1B1") (pin "2") (pinfunction "WIPER_2") (pintype "passive"))
      (node (ref "R3-1B1") (pin "3") (pinfunction "CW_3") (pintype "passive"))
      (node (ref "R3-2B1") (pin "1") (pinfunction "1_1") (pintype "passive"))
    )
    (net (code "81") (name "Net-(R3-1B2-CCW)") (class "Default")
      (node (ref "R2B2") (pin "1") (pinfunction "1_1") (pintype "passive"))
      (node (ref "R3-1B2") (pin "1") (pinfunction "CCW_1") (pintype "passive"))
      (node (ref "U3") (pin "2") (pinfunction "-IN_2") (pintype "input"))
    )
    (net (code "82") (name "Net-(R3-1B2-CW)") (class "Default")
      (node (ref "R3-1B2") (pin "2") (pinfunction "WIPER_2") (pintype "passive"))
      (node (ref "R3-1B2") (pin "3") (pinfunction "CW_3") (pintype "passive"))
      (node (ref "R3-2B2") (pin "1") (pinfunction "1_1") (pintype "passive"))
    )
    (net (code "83") (name "Net-(R3-2A1-Pad2)") (class "Default")
      (node (ref "R3-2A1") (pin "2") (pinfunction "2_2") (pintype "passive"))
      (node (ref "R3-3A1") (pin "1") (pinfunction "1_1") (pintype "passive"))
    )
    (net (code "84") (name "Net-(R3-2A2-Pad2)") (class "Default")
      (node (ref "R3-2A2") (pin "2") (pinfunction "2_2") (pintype "passive"))
      (node (ref "R3-3A2") (pin "1") (pinfunction "1_1") (pintype "passive"))
    )
    (net (code "85") (name "Net-(R3-2B1-Pad2)") (class "Default")
      (node (ref "R3-2B1") (pin "2") (pinfunction "2_2") (pintype "passive"))
      (node (ref "R3-3B1") (pin "1") (pinfunction "1_1") (pintype "passive"))
    )
    (net (code "86") (name "Net-(R3-2B2-Pad2)") (class "Default")
      (node (ref "R3-2B2") (pin "2") (pinfunction "2_2") (pintype "passive"))
      (node (ref "R3-3B2") (pin "1") (pinfunction "1_1") (pintype "passive"))
    )
    (net (code "87") (name "Net-(R7A-2)") (class "Default")
      (node (ref "LED1") (pin "A") (pinfunction "A_A") (pintype "passive"))
      (node (ref "R7") (pin "8") (pinfunction "2_8") (pintype "passive"))
    )
    (net (code "88") (name "Net-(R7B-2)") (class "Default")
      (node (ref "LED2") (pin "A") (pinfunction "A_A") (pintype "passive"))
      (node (ref "R7") (pin "7") (pinfunction "2_7") (pintype "passive"))
    )
    (net (code "89") (name "Net-(R7C-2)") (class "Default")
      (node (ref "LED3") (pin "A") (pinfunction "A_A") (pintype "passive"))
      (node (ref "R7") (pin "6") (pinfunction "2_6") (pintype "passive"))
    )
    (net (code "90") (name "Net-(R7D-2)") (class "Default")
      (node (ref "LED4") (pin "A") (pinfunction "A_A") (pintype "passive"))
      (node (ref "R7") (pin "5") (pinfunction "2_5") (pintype "passive"))
    )
    (net (code "91") (name "Net-(R15A-2)") (class "Default")
      (node (ref "LED5") (pin "A") (pinfunction "A_A") (pintype "passive"))
      (node (ref "R15") (pin "8") (pinfunction "2_8") (pintype "passive"))
    )
    (net (code "92") (name "Net-(R15B-2)") (class "Default")
      (node (ref "LED6") (pin "A") (pinfunction "A_A") (pintype "passive"))
      (node (ref "R15") (pin "7") (pinfunction "2_7") (pintype "passive"))
    )
    (net (code "93") (name "Net-(R15C-2)") (class "Default")
      (node (ref "LED7") (pin "A") (pinfunction "A_A") (pintype "passive"))
      (node (ref "R15") (pin "6") (pinfunction "2_6") (pintype "passive"))
    )
    (net (code "94") (name "Net-(R15D-2)") (class "Default")
      (node (ref "LED8") (pin "A") (pinfunction "A_A") (pintype "passive"))
      (node (ref "R15") (pin "5") (pinfunction "2_5") (pintype "passive"))
    )
    (net (code "95") (name "Net-(R19A-2)") (class "Default")
      (node (ref "LED9") (pin "A") (pinfunction "A_A") (pintype "passive"))
      (node (ref "R19") (pin "8") (pinfunction "2_8") (pintype "passive"))
    )
    (net (code "96") (name "Net-(R19B-2)") (class "Default")
      (node (ref "LED10") (pin "A") (pinfunction "A_A") (pintype "passive"))
      (node (ref "R19") (pin "7") (pinfunction "2_7") (pintype "passive"))
    )
    (net (code "97") (name "Net-(R19C-2)") (class "Default")
      (node (ref "LED11") (pin "A") (pinfunction "A_A") (pintype "passive"))
      (node (ref "R19") (pin "6") (pinfunction "2_6") (pintype "passive"))
    )
    (net (code "98") (name "Net-(R19D-2)") (class "Default")
      (node (ref "LED12") (pin "A") (pinfunction "A_A") (pintype "passive"))
      (node (ref "R19") (pin "5") (pinfunction "2_5") (pintype "passive"))
    )
    (net (code "99") (name "Net-(R22A-2)") (class "Default")
      (node (ref "LED13") (pin "A") (pinfunction "A_A") (pintype "passive"))
      (node (ref "R22") (pin "8") (pinfunction "2_8") (pintype "passive"))
    )
    (net (code "100") (name "Net-(R22B-2)") (class "Default")
      (node (ref "LED14") (pin "A") (pinfunction "A_A") (pintype "passive"))
      (node (ref "R22") (pin "7") (pinfunction "2_7") (pintype "passive"))
    )
    (net (code "101") (name "Net-(R22C-2)") (class "Default")
      (node (ref "LED15") (pin "A") (pinfunction "A_A") (pintype "passive"))
      (node (ref "R22") (pin "6") (pinfunction "2_6") (pintype "passive"))
    )
    (net (code "102") (name "Net-(R22D-2)") (class "Default")
      (node (ref "LED16") (pin "A") (pinfunction "A_A") (pintype "passive"))
      (node (ref "R22") (pin "5") (pinfunction "2_5") (pintype "passive"))
    )
    (net (code "103") (name "Net-(U1-A0)") (class "Default")
      (node (ref "JP1") (pin "2") (pinfunction "2_2") (pintype "passive"))
      (node (ref "U1") (pin "15") (pinfunction "A0_15") (pintype "input"))
    )
    (net (code "104") (name "Net-(U1-A1)") (class "Default")
      (node (ref "JP2") (pin "2") (pinfunction "2_2") (pintype "passive"))
      (node (ref "U1") (pin "16") (pinfunction "A1_16") (pintype "input"))
    )
    (net (code "105") (name "Net-(U1-A2)") (class "Default")
      (node (ref "JP3") (pin "2") (pinfunction "2_2") (pintype "passive"))
      (node (ref "U1") (pin "17") (pinfunction "A2_17") (pintype "input"))
    )
    (net (code "106") (name "Net-(U2A-+IN)") (class "Default")
      (node (ref "R4B1") (pin "2") (pinfunction "2_2") (pintype "passive"))
      (node (ref "U2") (pin "3") (pinfunction "+IN_3") (pintype "input"))
    )
    (net (code "107") (name "Net-(U2A-OUT)") (class "Default")
      (node (ref "R3-3B1") (pin "2") (pinfunction "2_2") (pintype "passive"))
      (node (ref "U2") (pin "1") (pinfunction "OUT_1") (pintype "output"))
      (node (ref "X5") (pin "1") (pinfunction "S_1") (pintype "passive"))
    )
    (net (code "108") (name "Net-(U2B-+IN)") (class "Default")
      (node (ref "R4A2") (pin "2") (pinfunction "2_2") (pintype "passive"))
      (node (ref "U2") (pin "5") (pinfunction "+IN_5") (pintype "input"))
    )
    (net (code "109") (name "Net-(U2B-OUT)") (class "Default")
      (node (ref "R3-3A1") (pin "2") (pinfunction "2_2") (pintype "passive"))
      (node (ref "U2") (pin "7") (pinfunction "OUT_7") (pintype "output"))
      (node (ref "X4") (pin "1") (pinfunction "S_1") (pintype "passive"))
    )
    (net (code "110") (name "Net-(U3A-+IN)") (class "Default")
      (node (ref "R4B2") (pin "2") (pinfunction "2_2") (pintype "passive"))
      (node (ref "U3") (pin "3") (pinfunction "+IN_3") (pintype "input"))
    )
    (net (code "111") (name "Net-(U3A-OUT)") (class "Default")
      (node (ref "R3-3B2") (pin "2") (pinfunction "2_2") (pintype "passive"))
      (node (ref "U3") (pin "1") (pinfunction "OUT_1") (pintype "output"))
      (node (ref "X7") (pin "1") (pinfunction "S_1") (pintype "passive"))
    )
    (net (code "112") (name "Net-(U3B-+IN)") (class "Default")
      (node (ref "R4A1") (pin "2") (pinfunction "2_2") (pintype "passive"))
      (node (ref "U3") (pin "5") (pinfunction "+IN_5") (pintype "input"))
    )
    (net (code "113") (name "Net-(U3B-OUT)") (class "Default")
      (node (ref "R3-3A2") (pin "2") (pinfunction "2_2") (pintype "passive"))
      (node (ref "U3") (pin "7") (pinfunction "OUT_7") (pintype "output"))
      (node (ref "X6") (pin "1") (pinfunction "S_1") (pintype "passive"))
    )
    (net (code "114") (name "Net-(X11A-S)") (class "Default")
      (node (ref "JP6") (pin "3") (pinfunction "3_3") (pintype "passive"))
      (node (ref "X11") (pin "1") (pinfunction "S_1") (pintype "passive"))
    )
    (net (code "115") (name "Net-(X11B-S)") (class "Default")
      (node (ref "JP6") (pin "2") (pinfunction "2_2") (pintype "passive"))
      (node (ref "X11") (pin "2") (pinfunction "S_2") (pintype "passive"))
    )
    (net (code "116") (name "Net-(X14A-S)") (class "Default")
      (node (ref "JP8") (pin "3") (pinfunction "3_3") (pintype "passive"))
      (node (ref "X14") (pin "1") (pinfunction "S_1") (pintype "passive"))
    )
    (net (code "117") (name "Net-(X14B-S)") (class "Default")
      (node (ref "JP8") (pin "2") (pinfunction "2_2") (pintype "passive"))
      (node (ref "X14") (pin "2") (pinfunction "S_2") (pintype "passive"))
    )
    (net (code "118") (name "Net-(X17A-S)") (class "Default")
      (node (ref "JP10") (pin "3") (pinfunction "3_3") (pintype "passive"))
      (node (ref "X17") (pin "1") (pinfunction "S_1") (pintype "passive"))
    )
    (net (code "119") (name "Net-(X17B-S)") (class "Default")
      (node (ref "JP10") (pin "2") (pinfunction "2_2") (pintype "passive"))
      (node (ref "X17") (pin "2") (pinfunction "S_2") (pintype "passive"))
    )
    (net (code "120") (name "unconnected-(U1-INTA-Pad20)") (class "Default")
      (node (ref "U1") (pin "20") (pinfunction "INTA_20") (pintype "output"))
    )
    (net (code "121") (name "unconnected-(U1-INTB-Pad19)") (class "Default")
      (node (ref "U1") (pin "19") (pinfunction "INTB_19") (pintype "output"))
    )
  )
)
